# STM32_microcontroller_IOs.net
KiCad netlist of a schematic drawn in Altium Designer
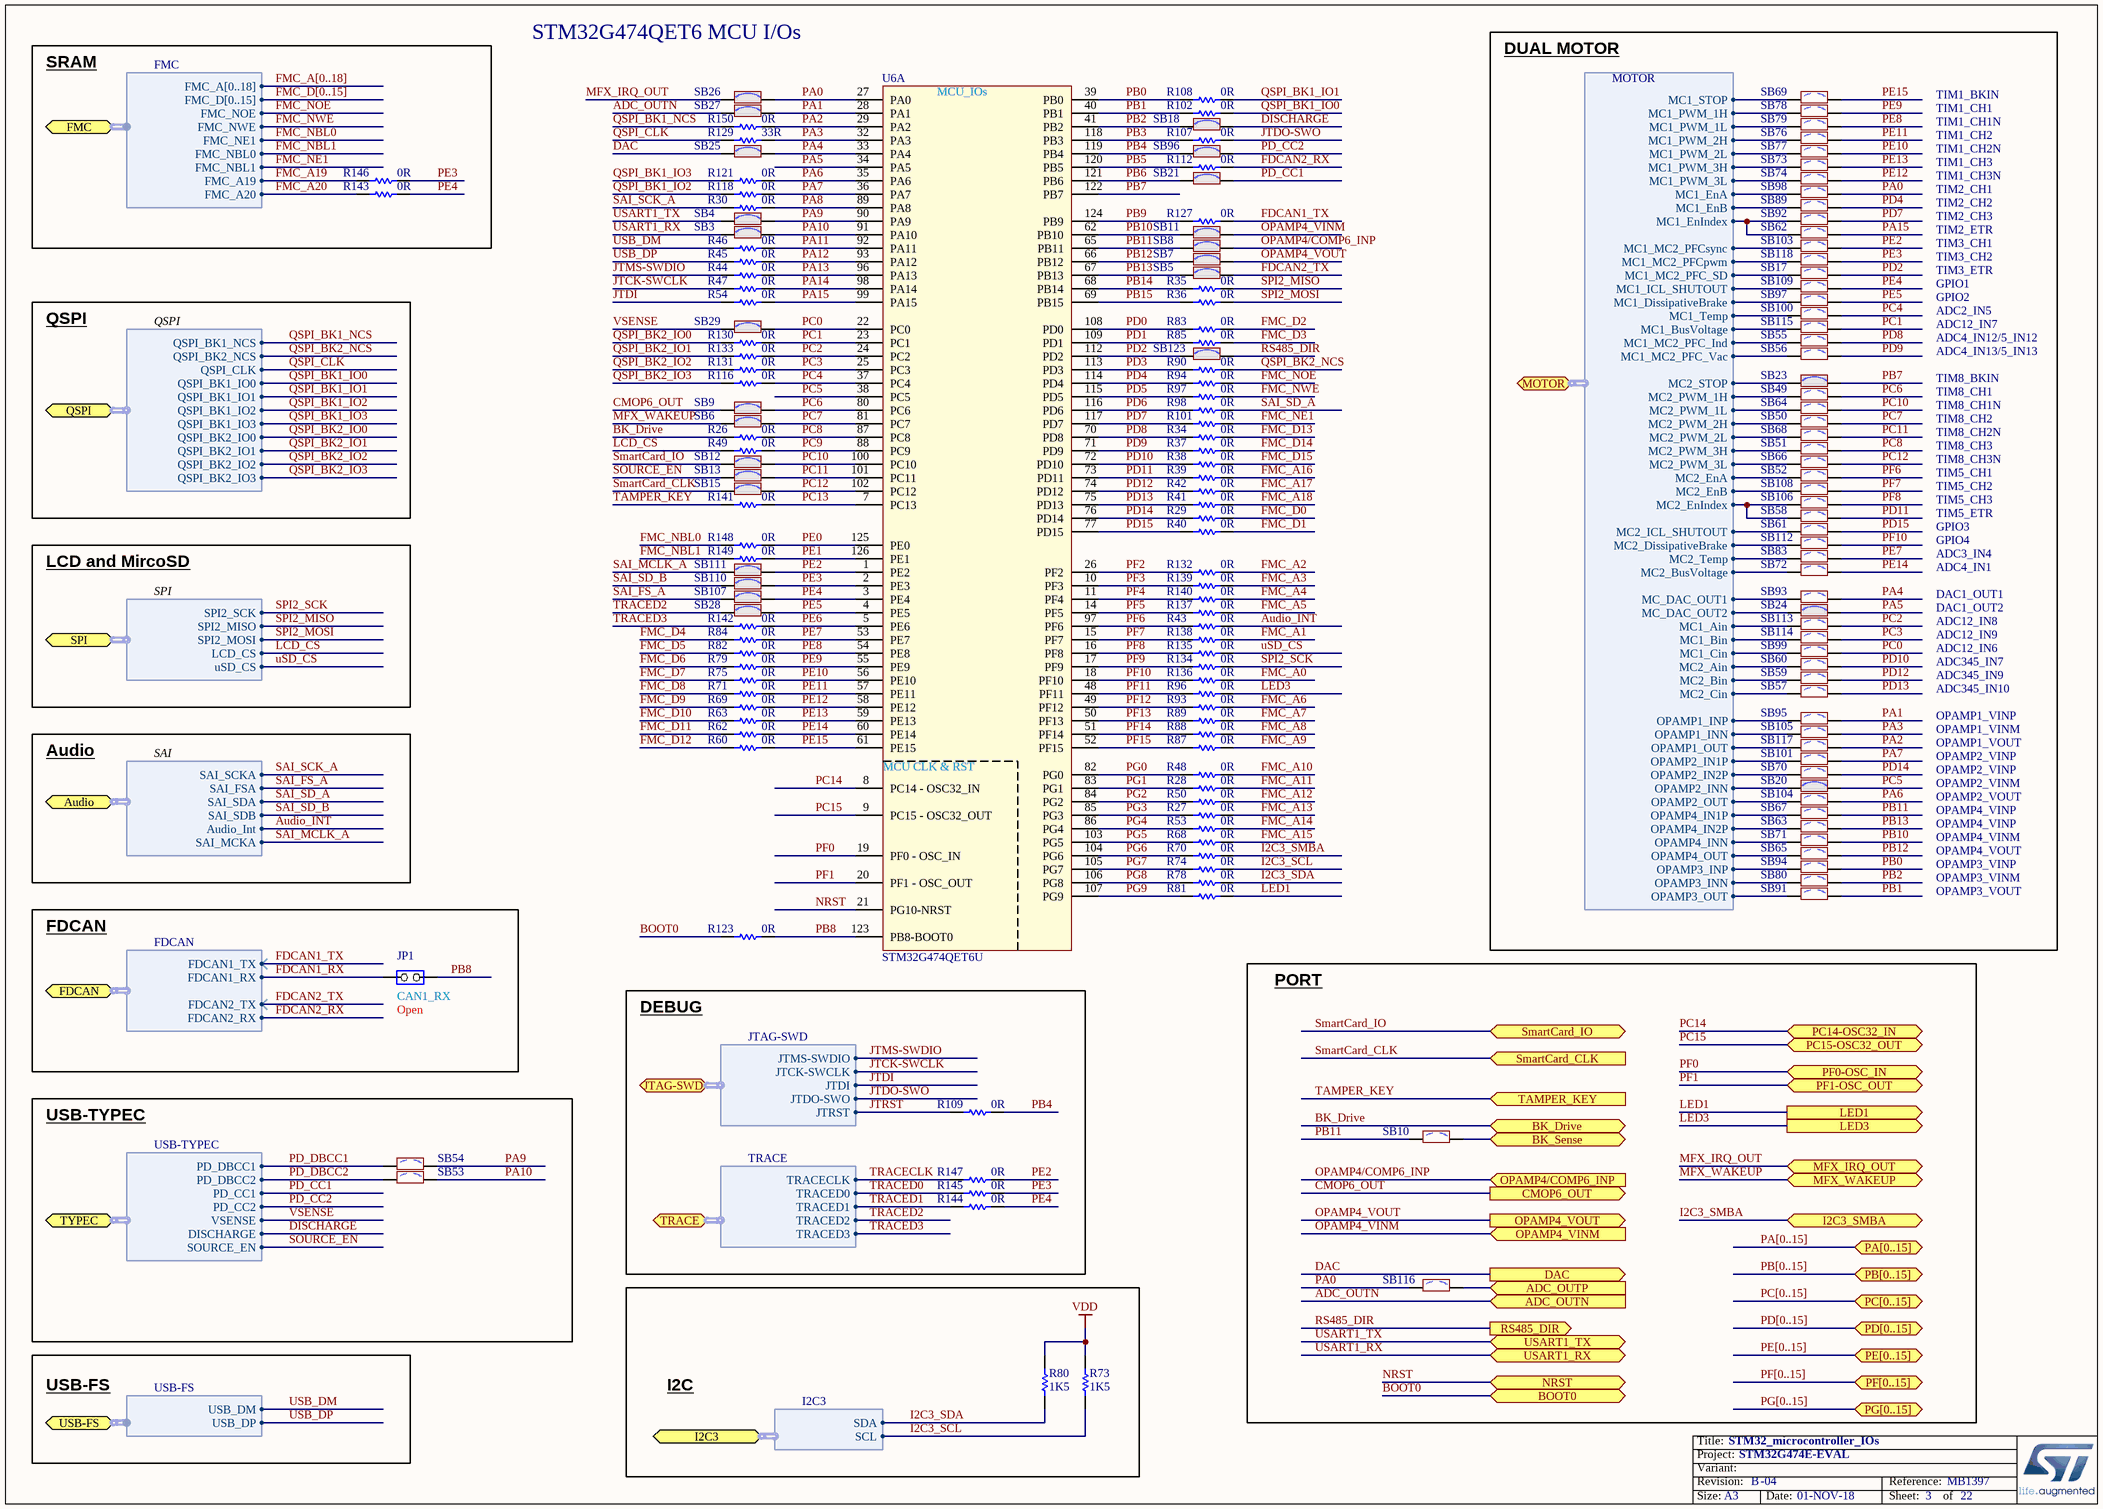
[diagram p0: STM32_microcontroller_IOs.SchDoc]

(export (version "E")
  (design (tool "Eeschema 10.0.6"))
  (components
    (comp (ref "JP1")
      (value "Jumper_Header 2x1")
      (footprint "CON_SAMTEC_TSW-102-07-G-S")
      (description "Header, 2x1, 2,54mm, VR, TH, Height 5.84mm/2.54mm")
      (fields
        (field (name "INTERNAL_PART_NUMBER") "MCD-00045")
        (field (name "MANUFACTURER_PART_NUMBER") "TSW-102-07-x-S")
        (field (name "PROVIDED_BY") "SUBCO")
      )
      (libsource (lib "MCD_PARTS_database") (part "Jumper_Header 2x1"))
    )
    (comp (ref "R26")
      (value "0R")
      (footprint "R0402")
      (description "Resistor,0R,0402,5%,1/16W")
      (fields
        (field (name "INTERNAL_PART_NUMBER") "MCD-00052")
        (field (name "MANUFACTURER_PART_NUMBER") "RC0402JR-070RL")
        (field (name "PROVIDED_BY") "SUBCO")
      )
      (libsource (lib "MCD_PARTS_database") (part "Resistor"))
    )
    (comp (ref "R27")
      (value "0R")
      (footprint "R0402")
      (description "Resistor,0R,0402,5%,1/16W")
      (fields (field (name "INTERNAL_PART_NUMBER") "MCD-00052") (field (name "Comment") "Resistor"))
      (libsource (lib "MCD_PARTS_database") (part "Resistor"))
    )
    (comp (ref "R28")
      (value "0R")
      (footprint "R0402")
      (description "Resistor,0R,0402,5%,1/16W")
      (fields (field (name "INTERNAL_PART_NUMBER") "MCD-00052") (field (name "Comment") "Resistor"))
      (libsource (lib "MCD_PARTS_database") (part "Resistor"))
    )
    (comp (ref "R29")
      (value "0R")
      (footprint "R0402")
      (description "Resistor,0R,0402,5%,1/16W")
      (fields (field (name "INTERNAL_PART_NUMBER") "MCD-00052") (field (name "Comment") "Resistor"))
      (libsource (lib "MCD_PARTS_database") (part "Resistor"))
    )
    (comp (ref "R30")
      (value "0R")
      (footprint "R0402")
      (description "Resistor,0R,0402,5%,1/16W")
      (fields
        (field (name "INTERNAL_PART_NUMBER") "MCD-00052")
        (field (name "MANUFACTURER_PART_NUMBER") "RC0402JR-070RL")
        (field (name "PROVIDED_BY") "SUBCO")
      )
      (libsource (lib "MCD_PARTS_database") (part "Resistor"))
    )
    (comp (ref "R34")
      (value "0R")
      (footprint "R0402")
      (description "Resistor,0R,0402,5%,1/16W")
      (fields (field (name "INTERNAL_PART_NUMBER") "MCD-00052") (field (name "Comment") "Resistor"))
      (libsource (lib "MCD_PARTS_database") (part "Resistor"))
    )
    (comp (ref "R35")
      (value "0R")
      (footprint "R0402")
      (description "Resistor,0R,0402,5%,1/16W")
      (fields
        (field (name "INTERNAL_PART_NUMBER") "MCD-00052")
        (field (name "MANUFACTURER_PART_NUMBER") "RC0402JR-070RL")
        (field (name "PROVIDED_BY") "SUBCO")
      )
      (libsource (lib "MCD_PARTS_database") (part "Resistor"))
    )
    (comp (ref "R36")
      (value "0R")
      (footprint "R0402")
      (description "Resistor,0R,0402,5%,1/16W")
      (fields
        (field (name "INTERNAL_PART_NUMBER") "MCD-00052")
        (field (name "MANUFACTURER_PART_NUMBER") "RC0402JR-070RL")
        (field (name "PROVIDED_BY") "SUBCO")
      )
      (libsource (lib "MCD_PARTS_database") (part "Resistor"))
    )
    (comp (ref "R37")
      (value "0R")
      (footprint "R0402")
      (description "Resistor,0R,0402,5%,1/16W")
      (fields (field (name "INTERNAL_PART_NUMBER") "MCD-00052") (field (name "Comment") "Resistor"))
      (libsource (lib "MCD_PARTS_database") (part "Resistor"))
    )
    (comp (ref "R38")
      (value "0R")
      (footprint "R0402")
      (description "Resistor,0R,0402,5%,1/16W")
      (fields (field (name "INTERNAL_PART_NUMBER") "MCD-00052") (field (name "Comment") "Resistor"))
      (libsource (lib "MCD_PARTS_database") (part "Resistor"))
    )
    (comp (ref "R39")
      (value "0R")
      (footprint "R0402")
      (description "Resistor,0R,0402,5%,1/16W")
      (fields (field (name "INTERNAL_PART_NUMBER") "MCD-00052") (field (name "Comment") "Resistor"))
      (libsource (lib "MCD_PARTS_database") (part "Resistor"))
    )
    (comp (ref "R40")
      (value "0R")
      (footprint "R0402")
      (description "Resistor,0R,0402,5%,1/16W")
      (fields (field (name "INTERNAL_PART_NUMBER") "MCD-00052") (field (name "Comment") "Resistor"))
      (libsource (lib "MCD_PARTS_database") (part "Resistor"))
    )
    (comp (ref "R41")
      (value "0R")
      (footprint "R0402")
      (description "Resistor,0R,0402,5%,1/16W")
      (fields (field (name "INTERNAL_PART_NUMBER") "MCD-00052") (field (name "Comment") "Resistor"))
      (libsource (lib "MCD_PARTS_database") (part "Resistor"))
    )
    (comp (ref "R42")
      (value "0R")
      (footprint "R0402")
      (description "Resistor,0R,0402,5%,1/16W")
      (fields (field (name "INTERNAL_PART_NUMBER") "MCD-00052") (field (name "Comment") "Resistor"))
      (libsource (lib "MCD_PARTS_database") (part "Resistor"))
    )
    (comp (ref "R43")
      (value "0R")
      (footprint "R0402")
      (description "Resistor,0R,0402,5%,1/16W")
      (fields
        (field (name "INTERNAL_PART_NUMBER") "MCD-00052")
        (field (name "MANUFACTURER_PART_NUMBER") "RC0402JR-070RL")
        (field (name "PROVIDED_BY") "SUBCO")
      )
      (libsource (lib "MCD_PARTS_database") (part "Resistor"))
    )
    (comp (ref "R44")
      (value "0R")
      (footprint "R0402")
      (description "Resistor,0R,0402,5%,1/16W")
      (fields
        (field (name "INTERNAL_PART_NUMBER") "MCD-00052")
        (field (name "MANUFACTURER_PART_NUMBER") "RC0402JR-070RL")
        (field (name "PROVIDED_BY") "SUBCO")
      )
      (libsource (lib "MCD_PARTS_database") (part "Resistor"))
    )
    (comp (ref "R45")
      (value "0R")
      (footprint "R0402")
      (description "Resistor,0R,0402,5%,1/16W")
      (fields
        (field (name "INTERNAL_PART_NUMBER") "MCD-00052")
        (field (name "MANUFACTURER_PART_NUMBER") "RC0402JR-070RL")
        (field (name "PROVIDED_BY") "SUBCO")
      )
      (libsource (lib "MCD_PARTS_database") (part "Resistor"))
    )
    (comp (ref "R46")
      (value "0R")
      (footprint "R0402")
      (description "Resistor,0R,0402,5%,1/16W")
      (fields
        (field (name "INTERNAL_PART_NUMBER") "MCD-00052")
        (field (name "MANUFACTURER_PART_NUMBER") "RC0402JR-070RL")
        (field (name "PROVIDED_BY") "SUBCO")
      )
      (libsource (lib "MCD_PARTS_database") (part "Resistor"))
    )
    (comp (ref "R47")
      (value "0R")
      (footprint "R0402")
      (description "Resistor,0R,0402,5%,1/16W")
      (fields
        (field (name "INTERNAL_PART_NUMBER") "MCD-00052")
        (field (name "MANUFACTURER_PART_NUMBER") "RC0402JR-070RL")
        (field (name "PROVIDED_BY") "SUBCO")
      )
      (libsource (lib "MCD_PARTS_database") (part "Resistor"))
    )
    (comp (ref "R48")
      (value "0R")
      (footprint "R0402")
      (description "Resistor,0R,0402,5%,1/16W")
      (fields (field (name "INTERNAL_PART_NUMBER") "MCD-00052") (field (name "Comment") "Resistor"))
      (libsource (lib "MCD_PARTS_database") (part "Resistor"))
    )
    (comp (ref "R49")
      (value "0R")
      (footprint "R0402")
      (description "Resistor,0R,0402,5%,1/16W")
      (fields
        (field (name "INTERNAL_PART_NUMBER") "MCD-00052")
        (field (name "MANUFACTURER_PART_NUMBER") "RC0402JR-070RL")
        (field (name "PROVIDED_BY") "SUBCO")
      )
      (libsource (lib "MCD_PARTS_database") (part "Resistor"))
    )
    (comp (ref "R50")
      (value "0R")
      (footprint "R0402")
      (description "Resistor,0R,0402,5%,1/16W")
      (fields (field (name "INTERNAL_PART_NUMBER") "MCD-00052") (field (name "Comment") "Resistor"))
      (libsource (lib "MCD_PARTS_database") (part "Resistor"))
    )
    (comp (ref "R53")
      (value "0R")
      (footprint "R0402")
      (description "Resistor,0R,0402,5%,1/16W")
      (fields (field (name "INTERNAL_PART_NUMBER") "MCD-00052") (field (name "Comment") "Resistor"))
      (libsource (lib "MCD_PARTS_database") (part "Resistor"))
    )
    (comp (ref "R54")
      (value "0R")
      (footprint "R0402")
      (description "Resistor,0R,0402,5%,1/16W")
      (fields
        (field (name "INTERNAL_PART_NUMBER") "MCD-00052")
        (field (name "MANUFACTURER_PART_NUMBER") "RC0402JR-070RL")
        (field (name "PROVIDED_BY") "SUBCO")
      )
      (libsource (lib "MCD_PARTS_database") (part "Resistor"))
    )
    (comp (ref "R60")
      (value "0R")
      (footprint "R0402")
      (description "Resistor,0R,0402,5%,1/16W")
      (fields (field (name "INTERNAL_PART_NUMBER") "MCD-00052") (field (name "Comment") "Resistor"))
      (libsource (lib "MCD_PARTS_database") (part "Resistor"))
    )
    (comp (ref "R62")
      (value "0R")
      (footprint "R0402")
      (description "Resistor,0R,0402,5%,1/16W")
      (fields (field (name "INTERNAL_PART_NUMBER") "MCD-00052") (field (name "Comment") "Resistor"))
      (libsource (lib "MCD_PARTS_database") (part "Resistor"))
    )
    (comp (ref "R63")
      (value "0R")
      (footprint "R0402")
      (description "Resistor,0R,0402,5%,1/16W")
      (fields (field (name "INTERNAL_PART_NUMBER") "MCD-00052") (field (name "Comment") "Resistor"))
      (libsource (lib "MCD_PARTS_database") (part "Resistor"))
    )
    (comp (ref "R68")
      (value "0R")
      (footprint "R0402")
      (description "Resistor,0R,0402,5%,1/16W")
      (fields (field (name "INTERNAL_PART_NUMBER") "MCD-00052") (field (name "Comment") "Resistor"))
      (libsource (lib "MCD_PARTS_database") (part "Resistor"))
    )
    (comp (ref "R69")
      (value "0R")
      (footprint "R0402")
      (description "Resistor,0R,0402,5%,1/16W")
      (fields (field (name "INTERNAL_PART_NUMBER") "MCD-00052") (field (name "Comment") "Resistor"))
      (libsource (lib "MCD_PARTS_database") (part "Resistor"))
    )
    (comp (ref "R70")
      (value "0R")
      (footprint "R0402")
      (description "Resistor,0R,0402,5%,1/16W")
      (fields
        (field (name "INTERNAL_PART_NUMBER") "MCD-00052")
        (field (name "MANUFACTURER_PART_NUMBER") "RC0402JR-070RL")
        (field (name "PROVIDED_BY") "SUBCO")
      )
      (libsource (lib "MCD_PARTS_database") (part "Resistor"))
    )
    (comp (ref "R71")
      (value "0R")
      (footprint "R0402")
      (description "Resistor,0R,0402,5%,1/16W")
      (fields (field (name "INTERNAL_PART_NUMBER") "MCD-00052") (field (name "Comment") "Resistor"))
      (libsource (lib "MCD_PARTS_database") (part "Resistor"))
    )
    (comp (ref "R73")
      (value "1K5")
      (footprint "R0603")
      (description "Resistor,1K5,0603,1%,1/10W")
      (fields
        (field (name "INTERNAL_PART_NUMBER") "MCD-00217")
        (field (name "MANUFACTURER_PART_NUMBER") "RC0603FR-071K5L")
        (field (name "PROVIDED_BY") "SUBCO")
      )
      (libsource (lib "MCD_PARTS_database") (part "Resistor"))
    )
    (comp (ref "R74")
      (value "0R")
      (footprint "R0402")
      (description "Resistor,0R,0402,5%,1/16W")
      (fields
        (field (name "INTERNAL_PART_NUMBER") "MCD-00052")
        (field (name "MANUFACTURER_PART_NUMBER") "RC0402JR-070RL")
        (field (name "PROVIDED_BY") "SUBCO")
      )
      (libsource (lib "MCD_PARTS_database") (part "Resistor"))
    )
    (comp (ref "R75")
      (value "0R")
      (footprint "R0402")
      (description "Resistor,0R,0402,5%,1/16W")
      (fields (field (name "INTERNAL_PART_NUMBER") "MCD-00052") (field (name "Comment") "Resistor"))
      (libsource (lib "MCD_PARTS_database") (part "Resistor"))
    )
    (comp (ref "R78")
      (value "0R")
      (footprint "R0402")
      (description "Resistor,0R,0402,5%,1/16W")
      (fields
        (field (name "INTERNAL_PART_NUMBER") "MCD-00052")
        (field (name "MANUFACTURER_PART_NUMBER") "RC0402JR-070RL")
        (field (name "PROVIDED_BY") "SUBCO")
      )
      (libsource (lib "MCD_PARTS_database") (part "Resistor"))
    )
    (comp (ref "R79")
      (value "0R")
      (footprint "R0402")
      (description "Resistor,0R,0402,5%,1/16W")
      (fields (field (name "INTERNAL_PART_NUMBER") "MCD-00052") (field (name "Comment") "Resistor"))
      (libsource (lib "MCD_PARTS_database") (part "Resistor"))
    )
    (comp (ref "R80")
      (value "1K5")
      (footprint "R0603")
      (description "Resistor,1K5,0603,1%,1/10W")
      (fields
        (field (name "INTERNAL_PART_NUMBER") "MCD-00217")
        (field (name "MANUFACTURER_PART_NUMBER") "RC0603FR-071K5L")
        (field (name "PROVIDED_BY") "SUBCO")
      )
      (libsource (lib "MCD_PARTS_database") (part "Resistor"))
    )
    (comp (ref "R81")
      (value "0R")
      (footprint "R0402")
      (description "Resistor,0R,0402,5%,1/16W")
      (fields
        (field (name "INTERNAL_PART_NUMBER") "MCD-00052")
        (field (name "MANUFACTURER_PART_NUMBER") "RC0402JR-070RL")
        (field (name "PROVIDED_BY") "SUBCO")
      )
      (libsource (lib "MCD_PARTS_database") (part "Resistor"))
    )
    (comp (ref "R82")
      (value "0R")
      (footprint "R0402")
      (description "Resistor,0R,0402,5%,1/16W")
      (fields (field (name "INTERNAL_PART_NUMBER") "MCD-00052") (field (name "Comment") "Resistor"))
      (libsource (lib "MCD_PARTS_database") (part "Resistor"))
    )
    (comp (ref "R83")
      (value "0R")
      (footprint "R0402")
      (description "Resistor,0R,0402,5%,1/16W")
      (fields (field (name "INTERNAL_PART_NUMBER") "MCD-00052") (field (name "Comment") "Resistor"))
      (libsource (lib "MCD_PARTS_database") (part "Resistor"))
    )
    (comp (ref "R84")
      (value "0R")
      (footprint "R0402")
      (description "Resistor,0R,0402,5%,1/16W")
      (fields (field (name "INTERNAL_PART_NUMBER") "MCD-00052") (field (name "Comment") "Resistor"))
      (libsource (lib "MCD_PARTS_database") (part "Resistor"))
    )
    (comp (ref "R85")
      (value "0R")
      (footprint "R0402")
      (description "Resistor,0R,0402,5%,1/16W")
      (fields (field (name "INTERNAL_PART_NUMBER") "MCD-00052") (field (name "Comment") "Resistor"))
      (libsource (lib "MCD_PARTS_database") (part "Resistor"))
    )
    (comp (ref "R87")
      (value "0R")
      (footprint "R0402")
      (description "Resistor,0R,0402,5%,1/16W")
      (fields (field (name "INTERNAL_PART_NUMBER") "MCD-00052") (field (name "Comment") "Resistor"))
      (libsource (lib "MCD_PARTS_database") (part "Resistor"))
    )
    (comp (ref "R88")
      (value "0R")
      (footprint "R0402")
      (description "Resistor,0R,0402,5%,1/16W")
      (fields (field (name "INTERNAL_PART_NUMBER") "MCD-00052") (field (name "Comment") "Resistor"))
      (libsource (lib "MCD_PARTS_database") (part "Resistor"))
    )
    (comp (ref "R89")
      (value "0R")
      (footprint "R0402")
      (description "Resistor,0R,0402,5%,1/16W")
      (fields (field (name "INTERNAL_PART_NUMBER") "MCD-00052") (field (name "Comment") "Resistor"))
      (libsource (lib "MCD_PARTS_database") (part "Resistor"))
    )
    (comp (ref "R90")
      (value "0R")
      (footprint "R0402")
      (description "Resistor,0R,0402,5%,1/16W")
      (fields (field (name "INTERNAL_PART_NUMBER") "MCD-00052") (field (name "Comment") "Resistor"))
      (libsource (lib "MCD_PARTS_database") (part "Resistor"))
    )
    (comp (ref "R93")
      (value "0R")
      (footprint "R0402")
      (description "Resistor,0R,0402,5%,1/16W")
      (fields (field (name "INTERNAL_PART_NUMBER") "MCD-00052") (field (name "Comment") "Resistor"))
      (libsource (lib "MCD_PARTS_database") (part "Resistor"))
    )
    (comp (ref "R94")
      (value "0R")
      (footprint "R0402")
      (description "Resistor,0R,0402,5%,1/16W")
      (fields
        (field (name "INTERNAL_PART_NUMBER") "MCD-00052")
        (field (name "MANUFACTURER_PART_NUMBER") "RC0402JR-070RL")
        (field (name "PROVIDED_BY") "SUBCO")
      )
      (libsource (lib "MCD_PARTS_database") (part "Resistor"))
    )
    (comp (ref "R96")
      (value "0R")
      (footprint "R0402")
      (description "Resistor,0R,0402,5%,1/16W")
      (fields
        (field (name "INTERNAL_PART_NUMBER") "MCD-00052")
        (field (name "MANUFACTURER_PART_NUMBER") "RC0402JR-070RL")
        (field (name "PROVIDED_BY") "SUBCO")
      )
      (libsource (lib "MCD_PARTS_database") (part "Resistor"))
    )
    (comp (ref "R97")
      (value "0R")
      (footprint "R0402")
      (description "Resistor,0R,0402,5%,1/16W")
      (fields
        (field (name "INTERNAL_PART_NUMBER") "MCD-00052")
        (field (name "MANUFACTURER_PART_NUMBER") "RC0402JR-070RL")
        (field (name "PROVIDED_BY") "SUBCO")
      )
      (libsource (lib "MCD_PARTS_database") (part "Resistor"))
    )
    (comp (ref "R98")
      (value "0R")
      (footprint "R0402")
      (description "Resistor,0R,0402,5%,1/16W")
      (fields
        (field (name "INTERNAL_PART_NUMBER") "MCD-00052")
        (field (name "MANUFACTURER_PART_NUMBER") "RC0402JR-070RL")
        (field (name "PROVIDED_BY") "SUBCO")
      )
      (libsource (lib "MCD_PARTS_database") (part "Resistor"))
    )
    (comp (ref "R101")
      (value "0R")
      (footprint "R0402")
      (description "Resistor,0R,0402,5%,1/16W")
      (fields
        (field (name "INTERNAL_PART_NUMBER") "MCD-00052")
        (field (name "MANUFACTURER_PART_NUMBER") "RC0402JR-070RL")
        (field (name "PROVIDED_BY") "SUBCO")
      )
      (libsource (lib "MCD_PARTS_database") (part "Resistor"))
    )
    (comp (ref "R102")
      (value "0R")
      (footprint "R0402")
      (description "Resistor,0R,0402,5%,1/16W")
      (fields (field (name "INTERNAL_PART_NUMBER") "MCD-00052") (field (name "Comment") "Resistor"))
      (libsource (lib "MCD_PARTS_database") (part "Resistor"))
    )
    (comp (ref "R107")
      (value "0R")
      (footprint "R0402")
      (description "Resistor,0R,0402,5%,1/16W")
      (fields
        (field (name "INTERNAL_PART_NUMBER") "MCD-00052")
        (field (name "MANUFACTURER_PART_NUMBER") "RC0402JR-070RL")
        (field (name "PROVIDED_BY") "SUBCO")
      )
      (libsource (lib "MCD_PARTS_database") (part "Resistor"))
    )
    (comp (ref "R108")
      (value "0R")
      (footprint "R0402")
      (description "Resistor,0R,0402,5%,1/16W")
      (fields (field (name "INTERNAL_PART_NUMBER") "MCD-00052") (field (name "Comment") "Resistor"))
      (libsource (lib "MCD_PARTS_database") (part "Resistor"))
    )
    (comp (ref "R109")
      (value "0R")
      (footprint "R0402")
      (description "Resistor,0R,0402,5%,1/16W")
      (fields
        (field (name "INTERNAL_PART_NUMBER") "MCD-00052")
        (field (name "MANUFACTURER_PART_NUMBER") "RC0402JR-070RL")
        (field (name "PROVIDED_BY") "SUBCO")
      )
      (libsource (lib "MCD_PARTS_database") (part "Resistor"))
    )
    (comp (ref "R112")
      (value "0R")
      (footprint "R0402")
      (description "Resistor,0R,0402,5%,1/16W")
      (fields
        (field (name "INTERNAL_PART_NUMBER") "MCD-00052")
        (field (name "MANUFACTURER_PART_NUMBER") "RC0402JR-070RL")
        (field (name "PROVIDED_BY") "SUBCO")
      )
      (libsource (lib "MCD_PARTS_database") (part "Resistor"))
    )
    (comp (ref "R116")
      (value "0R")
      (footprint "R0402")
      (description "Resistor,0R,0402,5%,1/16W")
      (fields (field (name "INTERNAL_PART_NUMBER") "MCD-00052") (field (name "Comment") "Resistor"))
      (libsource (lib "MCD_PARTS_database") (part "Resistor"))
    )
    (comp (ref "R118")
      (value "0R")
      (footprint "R0402")
      (description "Resistor,0R,0402,5%,1/16W")
      (fields (field (name "INTERNAL_PART_NUMBER") "MCD-00052") (field (name "Comment") "Resistor"))
      (libsource (lib "MCD_PARTS_database") (part "Resistor"))
    )
    (comp (ref "R121")
      (value "0R")
      (footprint "R0402")
      (description "Resistor,0R,0402,5%,1/16W")
      (fields (field (name "INTERNAL_PART_NUMBER") "MCD-00052") (field (name "Comment") "Resistor"))
      (libsource (lib "MCD_PARTS_database") (part "Resistor"))
    )
    (comp (ref "R123")
      (value "0R")
      (footprint "R0402")
      (description "Resistor,0R,0402,5%,1/16W")
      (fields
        (field (name "INTERNAL_PART_NUMBER") "MCD-00052")
        (field (name "MANUFACTURER_PART_NUMBER") "RC0402JR-070RL")
        (field (name "PROVIDED_BY") "SUBCO")
      )
      (libsource (lib "MCD_PARTS_database") (part "Resistor"))
    )
    (comp (ref "R127")
      (value "0R")
      (footprint "R0402")
      (description "Resistor,0R,0402,5%,1/16W")
      (fields
        (field (name "INTERNAL_PART_NUMBER") "MCD-00052")
        (field (name "MANUFACTURER_PART_NUMBER") "RC0402JR-070RL")
        (field (name "PROVIDED_BY") "SUBCO")
      )
      (libsource (lib "MCD_PARTS_database") (part "Resistor"))
    )
    (comp (ref "R129")
      (value "33R")
      (footprint "R0402")
      (description "Resistor,33R,0402,1%,1/16W")
      (fields
        (field (name "INTERNAL_PART_NUMBER") "MCD-00455")
        (field (name "MANUFACTURER_PART_NUMBER") "RC0402FR-0733RL")
        (field (name "PROVIDED_BY") "SUBCO")
      )
      (libsource (lib "MCD_PARTS_database") (part "Resistor"))
    )
    (comp (ref "R130")
      (value "0R")
      (footprint "R0402")
      (description "Resistor,0R,0402,5%,1/16W")
      (fields (field (name "INTERNAL_PART_NUMBER") "MCD-00052") (field (name "Comment") "Resistor"))
      (libsource (lib "MCD_PARTS_database") (part "Resistor"))
    )
    (comp (ref "R131")
      (value "0R")
      (footprint "R0402")
      (description "Resistor,0R,0402,5%,1/16W")
      (fields (field (name "INTERNAL_PART_NUMBER") "MCD-00052") (field (name "Comment") "Resistor"))
      (libsource (lib "MCD_PARTS_database") (part "Resistor"))
    )
    (comp (ref "R132")
      (value "0R")
      (footprint "R0402")
      (description "Resistor,0R,0402,5%,1/16W")
      (fields (field (name "INTERNAL_PART_NUMBER") "MCD-00052") (field (name "Comment") "Resistor"))
      (libsource (lib "MCD_PARTS_database") (part "Resistor"))
    )
    (comp (ref "R133")
      (value "0R")
      (footprint "R0402")
      (description "Resistor,0R,0402,5%,1/16W")
      (fields (field (name "INTERNAL_PART_NUMBER") "MCD-00052") (field (name "Comment") "Resistor"))
      (libsource (lib "MCD_PARTS_database") (part "Resistor"))
    )
    (comp (ref "R134")
      (value "0R")
      (footprint "R0402")
      (description "Resistor,0R,0402,5%,1/16W")
      (fields
        (field (name "INTERNAL_PART_NUMBER") "MCD-00052")
        (field (name "MANUFACTURER_PART_NUMBER") "RC0402JR-070RL")
        (field (name "PROVIDED_BY") "SUBCO")
      )
      (libsource (lib "MCD_PARTS_database") (part "Resistor"))
    )
    (comp (ref "R135")
      (value "0R")
      (footprint "R0402")
      (description "Resistor,0R,0402,5%,1/16W")
      (fields
        (field (name "INTERNAL_PART_NUMBER") "MCD-00052")
        (field (name "MANUFACTURER_PART_NUMBER") "RC0402JR-070RL")
        (field (name "PROVIDED_BY") "SUBCO")
      )
      (libsource (lib "MCD_PARTS_database") (part "Resistor"))
    )
    (comp (ref "R136")
      (value "0R")
      (footprint "R0402")
      (description "Resistor,0R,0402,5%,1/16W")
      (fields (field (name "INTERNAL_PART_NUMBER") "MCD-00052") (field (name "Comment") "Resistor"))
      (libsource (lib "MCD_PARTS_database") (part "Resistor"))
    )
    (comp (ref "R137")
      (value "0R")
      (footprint "R0402")
      (description "Resistor,0R,0402,5%,1/16W")
      (fields (field (name "INTERNAL_PART_NUMBER") "MCD-00052") (field (name "Comment") "Resistor"))
      (libsource (lib "MCD_PARTS_database") (part "Resistor"))
    )
    (comp (ref "R138")
      (value "0R")
      (footprint "R0402")
      (description "Resistor,0R,0402,5%,1/16W")
      (fields (field (name "INTERNAL_PART_NUMBER") "MCD-00052") (field (name "Comment") "Resistor"))
      (libsource (lib "MCD_PARTS_database") (part "Resistor"))
    )
    (comp (ref "R139")
      (value "0R")
      (footprint "R0402")
      (description "Resistor,0R,0402,5%,1/16W")
      (fields (field (name "INTERNAL_PART_NUMBER") "MCD-00052") (field (name "Comment") "Resistor"))
      (libsource (lib "MCD_PARTS_database") (part "Resistor"))
    )
    (comp (ref "R140")
      (value "0R")
      (footprint "R0402")
      (description "Resistor,0R,0402,5%,1/16W")
      (fields (field (name "INTERNAL_PART_NUMBER") "MCD-00052") (field (name "Comment") "Resistor"))
      (libsource (lib "MCD_PARTS_database") (part "Resistor"))
    )
    (comp (ref "R141")
      (value "0R")
      (footprint "R0402")
      (description "Resistor,0R,0402,5%,1/16W")
      (fields
        (field (name "INTERNAL_PART_NUMBER") "MCD-00052")
        (field (name "MANUFACTURER_PART_NUMBER") "RC0402JR-070RL")
        (field (name "PROVIDED_BY") "SUBCO")
      )
      (libsource (lib "MCD_PARTS_database") (part "Resistor"))
    )
    (comp (ref "R142")
      (value "0R")
      (footprint "R0402")
      (description "Resistor,0R,0402,5%,1/16W")
      (fields
        (field (name "INTERNAL_PART_NUMBER") "MCD-00052")
        (field (name "MANUFACTURER_PART_NUMBER") "RC0402JR-070RL")
        (field (name "PROVIDED_BY") "SUBCO")
      )
      (libsource (lib "MCD_PARTS_database") (part "Resistor"))
    )
    (comp (ref "R143")
      (value "0R")
      (footprint "R0402")
      (description "Resistor,0R,0402,5%,1/16W")
      (fields (field (name "INTERNAL_PART_NUMBER") "MCD-00052") (field (name "Comment") "Resistor"))
      (libsource (lib "MCD_PARTS_database") (part "Resistor"))
    )
    (comp (ref "R144")
      (value "0R")
      (footprint "R0402")
      (description "Resistor,0R,0402,5%,1/16W")
      (fields
        (field (name "INTERNAL_PART_NUMBER") "MCD-00052")
        (field (name "MANUFACTURER_PART_NUMBER") "RC0402JR-070RL")
        (field (name "PROVIDED_BY") "SUBCO")
      )
      (libsource (lib "MCD_PARTS_database") (part "Resistor"))
    )
    (comp (ref "R145")
      (value "0R")
      (footprint "R0402")
      (description "Resistor,0R,0402,5%,1/16W")
      (fields
        (field (name "INTERNAL_PART_NUMBER") "MCD-00052")
        (field (name "MANUFACTURER_PART_NUMBER") "RC0402JR-070RL")
        (field (name "PROVIDED_BY") "SUBCO")
      )
      (libsource (lib "MCD_PARTS_database") (part "Resistor"))
    )
    (comp (ref "R146")
      (value "0R")
      (footprint "R0402")
      (description "Resistor,0R,0402,5%,1/16W")
      (fields (field (name "INTERNAL_PART_NUMBER") "MCD-00052") (field (name "Comment") "Resistor"))
      (libsource (lib "MCD_PARTS_database") (part "Resistor"))
    )
    (comp (ref "R147")
      (value "0R")
      (footprint "R0402")
      (description "Resistor,0R,0402,5%,1/16W")
      (fields
        (field (name "INTERNAL_PART_NUMBER") "MCD-00052")
        (field (name "MANUFACTURER_PART_NUMBER") "RC0402JR-070RL")
        (field (name "PROVIDED_BY") "SUBCO")
      )
      (libsource (lib "MCD_PARTS_database") (part "Resistor"))
    )
    (comp (ref "R148")
      (value "0R")
      (footprint "R0402")
      (description "Resistor,0R,0402,5%,1/16W")
      (fields
        (field (name "INTERNAL_PART_NUMBER") "MCD-00052")
        (field (name "MANUFACTURER_PART_NUMBER") "RC0402JR-070RL")
        (field (name "PROVIDED_BY") "SUBCO")
      )
      (libsource (lib "MCD_PARTS_database") (part "Resistor"))
    )
    (comp (ref "R149")
      (value "0R")
      (footprint "R0402")
      (description "Resistor,0R,0402,5%,1/16W")
      (fields
        (field (name "INTERNAL_PART_NUMBER") "MCD-00052")
        (field (name "MANUFACTURER_PART_NUMBER") "RC0402JR-070RL")
        (field (name "PROVIDED_BY") "SUBCO")
      )
      (libsource (lib "MCD_PARTS_database") (part "Resistor"))
    )
    (comp (ref "R150")
      (value "0R")
      (footprint "R0402")
      (description "Resistor,0R,0402,5%,1/16W")
      (fields (field (name "INTERNAL_PART_NUMBER") "MCD-00052") (field (name "Comment") "Resistor"))
      (libsource (lib "MCD_PARTS_database") (part "Resistor"))
    )
    (comp (ref "SB3")
      (value "SB_ON")
      (footprint "SOLDER-BRIDGE_R0603-0R")
      (description "Solder Bridge ON")
      (fields
        (field (name "INTERNAL_PART_NUMBER") "MCD-00071")
        (field (name "MANUFACTURER_PART_NUMBER") "RC0603JR-070RL")
        (field (name "PROVIDED_BY") "SUBCO")
      )
      (libsource (lib "MCD_PARTS_database") (part "SB_ON"))
    )
    (comp (ref "SB4")
      (value "SB_ON")
      (footprint "SOLDER-BRIDGE_R0603-0R")
      (description "Solder Bridge ON")
      (fields
        (field (name "INTERNAL_PART_NUMBER") "MCD-00071")
        (field (name "MANUFACTURER_PART_NUMBER") "RC0603JR-070RL")
        (field (name "PROVIDED_BY") "SUBCO")
      )
      (libsource (lib "MCD_PARTS_database") (part "SB_ON"))
    )
    (comp (ref "SB5")
      (value "SB_ON")
      (footprint "SOLDER-BRIDGE_R0603-0R")
      (description "Solder Bridge ON")
      (fields
        (field (name "INTERNAL_PART_NUMBER") "MCD-00071")
        (field (name "MANUFACTURER_PART_NUMBER") "RC0603JR-070RL")
        (field (name "PROVIDED_BY") "SUBCO")
      )
      (libsource (lib "MCD_PARTS_database") (part "SB_ON"))
    )
    (comp (ref "SB6")
      (value "SB_ON")
      (footprint "SOLDER-BRIDGE_R0603-0R")
      (description "Solder Bridge ON")
      (fields
        (field (name "INTERNAL_PART_NUMBER") "MCD-00071")
        (field (name "MANUFACTURER_PART_NUMBER") "RC0603JR-070RL")
        (field (name "PROVIDED_BY") "SUBCO")
      )
      (libsource (lib "MCD_PARTS_database") (part "SB_ON"))
    )
    (comp (ref "SB7")
      (value "SB_ON")
      (footprint "SOLDER-BRIDGE_R0603-0R")
      (description "Solder Bridge ON")
      (fields
        (field (name "INTERNAL_PART_NUMBER") "MCD-00071")
        (field (name "MANUFACTURER_PART_NUMBER") "RC0603JR-070RL")
        (field (name "PROVIDED_BY") "SUBCO")
      )
      (libsource (lib "MCD_PARTS_database") (part "SB_ON"))
    )
    (comp (ref "SB8")
      (value "SB_ON")
      (footprint "SOLDER-BRIDGE_R0603-0R")
      (description "Solder Bridge ON")
      (fields
        (field (name "INTERNAL_PART_NUMBER") "MCD-00071")
        (field (name "MANUFACTURER_PART_NUMBER") "RC0603JR-070RL")
        (field (name "PROVIDED_BY") "SUBCO")
      )
      (libsource (lib "MCD_PARTS_database") (part "SB_ON"))
    )
    (comp (ref "SB9")
      (value "SB_ON")
      (footprint "SOLDER-BRIDGE_R0603-0R")
      (description "Solder Bridge ON")
      (fields
        (field (name "INTERNAL_PART_NUMBER") "MCD-00071")
        (field (name "MANUFACTURER_PART_NUMBER") "RC0603JR-070RL")
        (field (name "PROVIDED_BY") "SUBCO")
      )
      (libsource (lib "MCD_PARTS_database") (part "SB_ON"))
    )
    (comp (ref "SB10")
      (value "SB_OFF")
      (footprint "SOLDER-BRIDGE_R0603-0R")
      (description "Solder Bridge OFF")
      (fields
        (field (name "INTERNAL_PART_NUMBER") "MCD-00072")
        (field (name "MANUFACTURER_PART_NUMBER") "RC0603JR-070RL")
        (field (name "PROVIDED_BY") "SUBCO")
      )
      (libsource (lib "MCD_PARTS_database") (part "SB_OFF"))
    )
    (comp (ref "SB11")
      (value "SB_ON")
      (footprint "SOLDER-BRIDGE_R0603-0R")
      (description "Solder Bridge ON")
      (fields
        (field (name "INTERNAL_PART_NUMBER") "MCD-00071")
        (field (name "MANUFACTURER_PART_NUMBER") "RC0603JR-070RL")
        (field (name "PROVIDED_BY") "SUBCO")
      )
      (libsource (lib "MCD_PARTS_database") (part "SB_ON"))
    )
    (comp (ref "SB12")
      (value "SB_ON")
      (footprint "SOLDER-BRIDGE_R0603-0R")
      (description "Solder Bridge ON")
      (fields
        (field (name "INTERNAL_PART_NUMBER") "MCD-00071")
        (field (name "MANUFACTURER_PART_NUMBER") "RC0603JR-070RL")
        (field (name "PROVIDED_BY") "SUBCO")
      )
      (libsource (lib "MCD_PARTS_database") (part "SB_ON"))
    )
    (comp (ref "SB13")
      (value "SB_ON")
      (footprint "SOLDER-BRIDGE_R0603-0R")
      (description "Solder Bridge ON")
      (fields
        (field (name "INTERNAL_PART_NUMBER") "MCD-00071")
        (field (name "MANUFACTURER_PART_NUMBER") "RC0603JR-070RL")
        (field (name "PROVIDED_BY") "SUBCO")
      )
      (libsource (lib "MCD_PARTS_database") (part "SB_ON"))
    )
    (comp (ref "SB15")
      (value "SB_ON")
      (footprint "SOLDER-BRIDGE_R0603-0R")
      (description "Solder Bridge ON")
      (fields
        (field (name "INTERNAL_PART_NUMBER") "MCD-00071")
        (field (name "MANUFACTURER_PART_NUMBER") "RC0603JR-070RL")
        (field (name "PROVIDED_BY") "SUBCO")
      )
      (libsource (lib "MCD_PARTS_database") (part "SB_ON"))
    )
    (comp (ref "SB17")
      (value "SB_OFF")
      (footprint "SOLDER-BRIDGE_R0603-0R")
      (description "Solder Bridge OFF")
      (fields
        (field (name "INTERNAL_PART_NUMBER") "MCD-00072")
        (field (name "MANUFACTURER_PART_NUMBER") "RC0603JR-070RL")
        (field (name "PROVIDED_BY") "SUBCO")
      )
      (libsource (lib "MCD_PARTS_database") (part "SB_OFF"))
    )
    (comp (ref "SB18")
      (value "SB_ON")
      (footprint "SOLDER-BRIDGE_R0603-0R")
      (description "Solder Bridge ON")
      (fields
        (field (name "INTERNAL_PART_NUMBER") "MCD-00071")
        (field (name "MANUFACTURER_PART_NUMBER") "RC0603JR-070RL")
        (field (name "PROVIDED_BY") "SUBCO")
      )
      (libsource (lib "MCD_PARTS_database") (part "SB_ON"))
    )
    (comp (ref "SB20")
      (value "SB_ON")
      (footprint "SOLDER-BRIDGE_R0603-0R")
      (description "Solder Bridge ON")
      (fields
        (field (name "INTERNAL_PART_NUMBER") "MCD-00071")
        (field (name "MANUFACTURER_PART_NUMBER") "RC0603JR-070RL")
        (field (name "PROVIDED_BY") "SUBCO")
      )
      (libsource (lib "MCD_PARTS_database") (part "SB_ON"))
    )
    (comp (ref "SB21")
      (value "SB_ON")
      (footprint "SOLDER-BRIDGE_R0603-0R")
      (description "Solder Bridge ON")
      (fields
        (field (name "INTERNAL_PART_NUMBER") "MCD-00071")
        (field (name "MANUFACTURER_PART_NUMBER") "RC0603JR-070RL")
        (field (name "PROVIDED_BY") "SUBCO")
      )
      (libsource (lib "MCD_PARTS_database") (part "SB_ON"))
    )
    (comp (ref "SB23")
      (value "SB_ON")
      (footprint "SOLDER-BRIDGE_R0603-0R")
      (description "Solder Bridge ON")
      (fields
        (field (name "INTERNAL_PART_NUMBER") "MCD-00071")
        (field (name "MANUFACTURER_PART_NUMBER") "RC0603JR-070RL")
        (field (name "PROVIDED_BY") "SUBCO")
      )
      (libsource (lib "MCD_PARTS_database") (part "SB_ON"))
    )
    (comp (ref "SB24")
      (value "SB_ON")
      (footprint "SOLDER-BRIDGE_R0603-0R")
      (description "Solder Bridge ON")
      (fields
        (field (name "INTERNAL_PART_NUMBER") "MCD-00071")
        (field (name "MANUFACTURER_PART_NUMBER") "RC0603JR-070RL")
        (field (name "PROVIDED_BY") "SUBCO")
      )
      (libsource (lib "MCD_PARTS_database") (part "SB_ON"))
    )
    (comp (ref "SB25")
      (value "SB_ON")
      (footprint "SOLDER-BRIDGE_R0603-0R")
      (description "Solder Bridge ON")
      (fields
        (field (name "INTERNAL_PART_NUMBER") "MCD-00071")
        (field (name "MANUFACTURER_PART_NUMBER") "RC0603JR-070RL")
        (field (name "PROVIDED_BY") "SUBCO")
      )
      (libsource (lib "MCD_PARTS_database") (part "SB_ON"))
    )
    (comp (ref "SB26")
      (value "SB_ON")
      (footprint "SOLDER-BRIDGE_R0603-0R")
      (description "Solder Bridge ON")
      (fields
        (field (name "INTERNAL_PART_NUMBER") "MCD-00071")
        (field (name "MANUFACTURER_PART_NUMBER") "RC0603JR-070RL")
        (field (name "PROVIDED_BY") "SUBCO")
      )
      (libsource (lib "MCD_PARTS_database") (part "SB_ON"))
    )
    (comp (ref "SB27")
      (value "SB_ON")
      (footprint "SOLDER-BRIDGE_R0603-0R")
      (description "Solder Bridge ON")
      (fields
        (field (name "INTERNAL_PART_NUMBER") "MCD-00071")
        (field (name "MANUFACTURER_PART_NUMBER") "RC0603JR-070RL")
        (field (name "PROVIDED_BY") "SUBCO")
      )
      (libsource (lib "MCD_PARTS_database") (part "SB_ON"))
    )
    (comp (ref "SB28")
      (value "SB_ON")
      (footprint "SOLDER-BRIDGE_R0603-0R")
      (description "Solder Bridge ON")
      (fields
        (field (name "INTERNAL_PART_NUMBER") "MCD-00071")
        (field (name "MANUFACTURER_PART_NUMBER") "RC0603JR-070RL")
        (field (name "PROVIDED_BY") "SUBCO")
      )
      (libsource (lib "MCD_PARTS_database") (part "SB_ON"))
    )
    (comp (ref "SB29")
      (value "SB_ON")
      (footprint "SOLDER-BRIDGE_R0603-0R")
      (description "Solder Bridge ON")
      (fields
        (field (name "INTERNAL_PART_NUMBER") "MCD-00071")
        (field (name "MANUFACTURER_PART_NUMBER") "RC0603JR-070RL")
        (field (name "PROVIDED_BY") "SUBCO")
      )
      (libsource (lib "MCD_PARTS_database") (part "SB_ON"))
    )
    (comp (ref "SB49")
      (value "SB_OFF")
      (footprint "SOLDER-BRIDGE_R0603-0R")
      (description "Solder Bridge OFF")
      (fields
        (field (name "INTERNAL_PART_NUMBER") "MCD-00072")
        (field (name "MANUFACTURER_PART_NUMBER") "RC0603JR-070RL")
        (field (name "PROVIDED_BY") "SUBCO")
      )
      (libsource (lib "MCD_PARTS_database") (part "SB_OFF"))
    )
    (comp (ref "SB50")
      (value "SB_OFF")
      (footprint "SOLDER-BRIDGE_R0603-0R")
      (description "Solder Bridge OFF")
      (fields
        (field (name "INTERNAL_PART_NUMBER") "MCD-00072")
        (field (name "MANUFACTURER_PART_NUMBER") "RC0603JR-070RL")
        (field (name "PROVIDED_BY") "SUBCO")
      )
      (libsource (lib "MCD_PARTS_database") (part "SB_OFF"))
    )
    (comp (ref "SB51")
      (value "SB_OFF")
      (footprint "SOLDER-BRIDGE_R0603-0R")
      (description "Solder Bridge OFF")
      (fields
        (field (name "INTERNAL_PART_NUMBER") "MCD-00072")
        (field (name "MANUFACTURER_PART_NUMBER") "RC0603JR-070RL")
        (field (name "PROVIDED_BY") "SUBCO")
      )
      (libsource (lib "MCD_PARTS_database") (part "SB_OFF"))
    )
    (comp (ref "SB52")
      (value "SB_OFF")
      (footprint "SOLDER-BRIDGE_R0603-0R")
      (description "Solder Bridge OFF")
      (fields
        (field (name "INTERNAL_PART_NUMBER") "MCD-00072")
        (field (name "MANUFACTURER_PART_NUMBER") "RC0603JR-070RL")
        (field (name "PROVIDED_BY") "SUBCO")
      )
      (libsource (lib "MCD_PARTS_database") (part "SB_OFF"))
    )
    (comp (ref "SB53")
      (value "SB_OFF")
      (footprint "SOLDER-BRIDGE_R0603-0R")
      (description "Solder Bridge OFF")
      (fields
        (field (name "INTERNAL_PART_NUMBER") "MCD-00072")
        (field (name "MANUFACTURER_PART_NUMBER") "RC0603JR-070RL")
        (field (name "PROVIDED_BY") "SUBCO")
      )
      (libsource (lib "MCD_PARTS_database") (part "SB_OFF"))
    )
    (comp (ref "SB54")
      (value "SB_OFF")
      (footprint "SOLDER-BRIDGE_R0603-0R")
      (description "Solder Bridge OFF")
      (fields
        (field (name "INTERNAL_PART_NUMBER") "MCD-00072")
        (field (name "MANUFACTURER_PART_NUMBER") "RC0603JR-070RL")
        (field (name "PROVIDED_BY") "SUBCO")
      )
      (libsource (lib "MCD_PARTS_database") (part "SB_OFF"))
    )
    (comp (ref "SB55")
      (value "SB_OFF")
      (footprint "SOLDER-BRIDGE_R0603-0R")
      (description "Solder Bridge OFF")
      (fields
        (field (name "INTERNAL_PART_NUMBER") "MCD-00072")
        (field (name "MANUFACTURER_PART_NUMBER") "RC0603JR-070RL")
        (field (name "PROVIDED_BY") "SUBCO")
      )
      (libsource (lib "MCD_PARTS_database") (part "SB_OFF"))
    )
    (comp (ref "SB56")
      (value "SB_OFF")
      (footprint "SOLDER-BRIDGE_R0603-0R")
      (description "Solder Bridge OFF")
      (fields
        (field (name "INTERNAL_PART_NUMBER") "MCD-00072")
        (field (name "MANUFACTURER_PART_NUMBER") "RC0603JR-070RL")
        (field (name "PROVIDED_BY") "SUBCO")
      )
      (libsource (lib "MCD_PARTS_database") (part "SB_OFF"))
    )
    (comp (ref "SB57")
      (value "SB_OFF")
      (footprint "SOLDER-BRIDGE_R0603-0R")
      (description "Solder Bridge OFF")
      (fields
        (field (name "INTERNAL_PART_NUMBER") "MCD-00072")
        (field (name "MANUFACTURER_PART_NUMBER") "RC0603JR-070RL")
        (field (name "PROVIDED_BY") "SUBCO")
      )
      (libsource (lib "MCD_PARTS_database") (part "SB_OFF"))
    )
    (comp (ref "SB58")
      (value "SB_OFF")
      (footprint "SOLDER-BRIDGE_R0603-0R")
      (description "Solder Bridge OFF")
      (fields
        (field (name "INTERNAL_PART_NUMBER") "MCD-00072")
        (field (name "MANUFACTURER_PART_NUMBER") "RC0603JR-070RL")
        (field (name "PROVIDED_BY") "SUBCO")
      )
      (libsource (lib "MCD_PARTS_database") (part "SB_OFF"))
    )
    (comp (ref "SB59")
      (value "SB_OFF")
      (footprint "SOLDER-BRIDGE_R0603-0R")
      (description "Solder Bridge OFF")
      (fields
        (field (name "INTERNAL_PART_NUMBER") "MCD-00072")
        (field (name "MANUFACTURER_PART_NUMBER") "RC0603JR-070RL")
        (field (name "PROVIDED_BY") "SUBCO")
      )
      (libsource (lib "MCD_PARTS_database") (part "SB_OFF"))
    )
    (comp (ref "SB60")
      (value "SB_OFF")
      (footprint "SOLDER-BRIDGE_R0603-0R")
      (description "Solder Bridge OFF")
      (fields
        (field (name "INTERNAL_PART_NUMBER") "MCD-00072")
        (field (name "MANUFACTURER_PART_NUMBER") "RC0603JR-070RL")
        (field (name "PROVIDED_BY") "SUBCO")
      )
      (libsource (lib "MCD_PARTS_database") (part "SB_OFF"))
    )
    (comp (ref "SB61")
      (value "SB_OFF")
      (footprint "SOLDER-BRIDGE_R0603-0R")
      (description "Solder Bridge OFF")
      (fields
        (field (name "INTERNAL_PART_NUMBER") "MCD-00072")
        (field (name "MANUFACTURER_PART_NUMBER") "RC0603JR-070RL")
        (field (name "PROVIDED_BY") "SUBCO")
      )
      (libsource (lib "MCD_PARTS_database") (part "SB_OFF"))
    )
    (comp (ref "SB62")
      (value "SB_OFF")
      (footprint "SOLDER-BRIDGE_R0603-0R")
      (description "Solder Bridge OFF")
      (fields
        (field (name "INTERNAL_PART_NUMBER") "MCD-00072")
        (field (name "MANUFACTURER_PART_NUMBER") "RC0603JR-070RL")
        (field (name "PROVIDED_BY") "SUBCO")
      )
      (libsource (lib "MCD_PARTS_database") (part "SB_OFF"))
    )
    (comp (ref "SB63")
      (value "SB_OFF")
      (footprint "SOLDER-BRIDGE_R0603-0R")
      (description "Solder Bridge OFF")
      (fields
        (field (name "INTERNAL_PART_NUMBER") "MCD-00072")
        (field (name "MANUFACTURER_PART_NUMBER") "RC0603JR-070RL")
        (field (name "PROVIDED_BY") "SUBCO")
      )
      (libsource (lib "MCD_PARTS_database") (part "SB_OFF"))
    )
    (comp (ref "SB64")
      (value "SB_OFF")
      (footprint "SOLDER-BRIDGE_R0603-0R")
      (description "Solder Bridge OFF")
      (fields
        (field (name "INTERNAL_PART_NUMBER") "MCD-00072")
        (field (name "MANUFACTURER_PART_NUMBER") "RC0603JR-070RL")
        (field (name "PROVIDED_BY") "SUBCO")
      )
      (libsource (lib "MCD_PARTS_database") (part "SB_OFF"))
    )
    (comp (ref "SB65")
      (value "SB_OFF")
      (footprint "SOLDER-BRIDGE_R0603-0R")
      (description "Solder Bridge OFF")
      (fields
        (field (name "INTERNAL_PART_NUMBER") "MCD-00072")
        (field (name "MANUFACTURER_PART_NUMBER") "RC0603JR-070RL")
        (field (name "PROVIDED_BY") "SUBCO")
      )
      (libsource (lib "MCD_PARTS_database") (part "SB_OFF"))
    )
    (comp (ref "SB66")
      (value "SB_OFF")
      (footprint "SOLDER-BRIDGE_R0603-0R")
      (description "Solder Bridge OFF")
      (fields
        (field (name "INTERNAL_PART_NUMBER") "MCD-00072")
        (field (name "MANUFACTURER_PART_NUMBER") "RC0603JR-070RL")
        (field (name "PROVIDED_BY") "SUBCO")
      )
      (libsource (lib "MCD_PARTS_database") (part "SB_OFF"))
    )
    (comp (ref "SB67")
      (value "SB_OFF")
      (footprint "SOLDER-BRIDGE_R0603-0R")
      (description "Solder Bridge OFF")
      (fields
        (field (name "INTERNAL_PART_NUMBER") "MCD-00072")
        (field (name "MANUFACTURER_PART_NUMBER") "RC0603JR-070RL")
        (field (name "PROVIDED_BY") "SUBCO")
      )
      (libsource (lib "MCD_PARTS_database") (part "SB_OFF"))
    )
    (comp (ref "SB68")
      (value "SB_OFF")
      (footprint "SOLDER-BRIDGE_R0603-0R")
      (description "Solder Bridge OFF")
      (fields
        (field (name "INTERNAL_PART_NUMBER") "MCD-00072")
        (field (name "MANUFACTURER_PART_NUMBER") "RC0603JR-070RL")
        (field (name "PROVIDED_BY") "SUBCO")
      )
      (libsource (lib "MCD_PARTS_database") (part "SB_OFF"))
    )
    (comp (ref "SB69")
      (value "SB_OFF")
      (footprint "SOLDER-BRIDGE_R0603-0R")
      (description "Solder Bridge OFF")
      (fields
        (field (name "INTERNAL_PART_NUMBER") "MCD-00072")
        (field (name "MANUFACTURER_PART_NUMBER") "RC0603JR-070RL")
        (field (name "PROVIDED_BY") "SUBCO")
      )
      (libsource (lib "MCD_PARTS_database") (part "SB_OFF"))
    )
    (comp (ref "SB70")
      (value "SB_OFF")
      (footprint "SOLDER-BRIDGE_R0603-0R")
      (description "Solder Bridge OFF")
      (fields
        (field (name "INTERNAL_PART_NUMBER") "MCD-00072")
        (field (name "MANUFACTURER_PART_NUMBER") "RC0603JR-070RL")
        (field (name "PROVIDED_BY") "SUBCO")
      )
      (libsource (lib "MCD_PARTS_database") (part "SB_OFF"))
    )
    (comp (ref "SB71")
      (value "SB_OFF")
      (footprint "SOLDER-BRIDGE_R0603-0R")
      (description "Solder Bridge OFF")
      (fields
        (field (name "INTERNAL_PART_NUMBER") "MCD-00072")
        (field (name "MANUFACTURER_PART_NUMBER") "RC0603JR-070RL")
        (field (name "PROVIDED_BY") "SUBCO")
      )
      (libsource (lib "MCD_PARTS_database") (part "SB_OFF"))
    )
    (comp (ref "SB72")
      (value "SB_OFF")
      (footprint "SOLDER-BRIDGE_R0603-0R")
      (description "Solder Bridge OFF")
      (fields
        (field (name "INTERNAL_PART_NUMBER") "MCD-00072")
        (field (name "MANUFACTURER_PART_NUMBER") "RC0603JR-070RL")
        (field (name "PROVIDED_BY") "SUBCO")
      )
      (libsource (lib "MCD_PARTS_database") (part "SB_OFF"))
    )
    (comp (ref "SB73")
      (value "SB_OFF")
      (footprint "SOLDER-BRIDGE_R0603-0R")
      (description "Solder Bridge OFF")
      (fields
        (field (name "INTERNAL_PART_NUMBER") "MCD-00072")
        (field (name "MANUFACTURER_PART_NUMBER") "RC0603JR-070RL")
        (field (name "PROVIDED_BY") "SUBCO")
      )
      (libsource (lib "MCD_PARTS_database") (part "SB_OFF"))
    )
    (comp (ref "SB74")
      (value "SB_OFF")
      (footprint "SOLDER-BRIDGE_R0603-0R")
      (description "Solder Bridge OFF")
      (fields
        (field (name "INTERNAL_PART_NUMBER") "MCD-00072")
        (field (name "MANUFACTURER_PART_NUMBER") "RC0603JR-070RL")
        (field (name "PROVIDED_BY") "SUBCO")
      )
      (libsource (lib "MCD_PARTS_database") (part "SB_OFF"))
    )
    (comp (ref "SB76")
      (value "SB_OFF")
      (footprint "SOLDER-BRIDGE_R0603-0R")
      (description "Solder Bridge OFF")
      (fields
        (field (name "INTERNAL_PART_NUMBER") "MCD-00072")
        (field (name "MANUFACTURER_PART_NUMBER") "RC0603JR-070RL")
        (field (name "PROVIDED_BY") "SUBCO")
      )
      (libsource (lib "MCD_PARTS_database") (part "SB_OFF"))
    )
    (comp (ref "SB77")
      (value "SB_OFF")
      (footprint "SOLDER-BRIDGE_R0603-0R")
      (description "Solder Bridge OFF")
      (fields
        (field (name "INTERNAL_PART_NUMBER") "MCD-00072")
        (field (name "MANUFACTURER_PART_NUMBER") "RC0603JR-070RL")
        (field (name "PROVIDED_BY") "SUBCO")
      )
      (libsource (lib "MCD_PARTS_database") (part "SB_OFF"))
    )
    (comp (ref "SB78")
      (value "SB_OFF")
      (footprint "SOLDER-BRIDGE_R0603-0R")
      (description "Solder Bridge OFF")
      (fields
        (field (name "INTERNAL_PART_NUMBER") "MCD-00072")
        (field (name "MANUFACTURER_PART_NUMBER") "RC0603JR-070RL")
        (field (name "PROVIDED_BY") "SUBCO")
      )
      (libsource (lib "MCD_PARTS_database") (part "SB_OFF"))
    )
    (comp (ref "SB79")
      (value "SB_OFF")
      (footprint "SOLDER-BRIDGE_R0603-0R")
      (description "Solder Bridge OFF")
      (fields
        (field (name "INTERNAL_PART_NUMBER") "MCD-00072")
        (field (name "MANUFACTURER_PART_NUMBER") "RC0603JR-070RL")
        (field (name "PROVIDED_BY") "SUBCO")
      )
      (libsource (lib "MCD_PARTS_database") (part "SB_OFF"))
    )
    (comp (ref "SB80")
      (value "SB_OFF")
      (footprint "SOLDER-BRIDGE_R0603-0R")
      (description "Solder Bridge OFF")
      (fields
        (field (name "INTERNAL_PART_NUMBER") "MCD-00072")
        (field (name "MANUFACTURER_PART_NUMBER") "RC0603JR-070RL")
        (field (name "PROVIDED_BY") "SUBCO")
      )
      (libsource (lib "MCD_PARTS_database") (part "SB_OFF"))
    )
    (comp (ref "SB83")
      (value "SB_OFF")
      (footprint "SOLDER-BRIDGE_R0603-0R")
      (description "Solder Bridge OFF")
      (fields
        (field (name "INTERNAL_PART_NUMBER") "MCD-00072")
        (field (name "MANUFACTURER_PART_NUMBER") "RC0603JR-070RL")
        (field (name "PROVIDED_BY") "SUBCO")
      )
      (libsource (lib "MCD_PARTS_database") (part "SB_OFF"))
    )
    (comp (ref "SB89")
      (value "SB_OFF")
      (footprint "SOLDER-BRIDGE_R0603-0R")
      (description "Solder Bridge OFF")
      (fields
        (field (name "INTERNAL_PART_NUMBER") "MCD-00072")
        (field (name "MANUFACTURER_PART_NUMBER") "RC0603JR-070RL")
        (field (name "PROVIDED_BY") "SUBCO")
      )
      (libsource (lib "MCD_PARTS_database") (part "SB_OFF"))
    )
    (comp (ref "SB91")
      (value "SB_OFF")
      (footprint "SOLDER-BRIDGE_R0603-0R")
      (description "Solder Bridge OFF")
      (fields
        (field (name "INTERNAL_PART_NUMBER") "MCD-00072")
        (field (name "MANUFACTURER_PART_NUMBER") "RC0603JR-070RL")
        (field (name "PROVIDED_BY") "SUBCO")
      )
      (libsource (lib "MCD_PARTS_database") (part "SB_OFF"))
    )
    (comp (ref "SB92")
      (value "SB_OFF")
      (footprint "SOLDER-BRIDGE_R0603-0R")
      (description "Solder Bridge OFF")
      (fields
        (field (name "INTERNAL_PART_NUMBER") "MCD-00072")
        (field (name "MANUFACTURER_PART_NUMBER") "RC0603JR-070RL")
        (field (name "PROVIDED_BY") "SUBCO")
      )
      (libsource (lib "MCD_PARTS_database") (part "SB_OFF"))
    )
    (comp (ref "SB93")
      (value "SB_OFF")
      (footprint "SOLDER-BRIDGE_R0603-0R")
      (description "Solder Bridge OFF")
      (fields
        (field (name "INTERNAL_PART_NUMBER") "MCD-00072")
        (field (name "MANUFACTURER_PART_NUMBER") "RC0603JR-070RL")
        (field (name "PROVIDED_BY") "SUBCO")
      )
      (libsource (lib "MCD_PARTS_database") (part "SB_OFF"))
    )
    (comp (ref "SB94")
      (value "SB_OFF")
      (footprint "SOLDER-BRIDGE_R0603-0R")
      (description "Solder Bridge OFF")
      (fields
        (field (name "INTERNAL_PART_NUMBER") "MCD-00072")
        (field (name "MANUFACTURER_PART_NUMBER") "RC0603JR-070RL")
        (field (name "PROVIDED_BY") "SUBCO")
      )
      (libsource (lib "MCD_PARTS_database") (part "SB_OFF"))
    )
    (comp (ref "SB95")
      (value "SB_OFF")
      (footprint "SOLDER-BRIDGE_R0603-0R")
      (description "Solder Bridge OFF")
      (fields
        (field (name "INTERNAL_PART_NUMBER") "MCD-00072")
        (field (name "MANUFACTURER_PART_NUMBER") "RC0603JR-070RL")
        (field (name "PROVIDED_BY") "SUBCO")
      )
      (libsource (lib "MCD_PARTS_database") (part "SB_OFF"))
    )
    (comp (ref "SB96")
      (value "SB_ON")
      (footprint "SOLDER-BRIDGE_R0603-0R")
      (description "Solder Bridge ON")
      (fields
        (field (name "INTERNAL_PART_NUMBER") "MCD-00071")
        (field (name "MANUFACTURER_PART_NUMBER") "RC0603JR-070RL")
        (field (name "PROVIDED_BY") "SUBCO")
      )
      (libsource (lib "MCD_PARTS_database") (part "SB_ON"))
    )
    (comp (ref "SB97")
      (value "SB_OFF")
      (footprint "SOLDER-BRIDGE_R0603-0R")
      (description "Solder Bridge OFF")
      (fields
        (field (name "INTERNAL_PART_NUMBER") "MCD-00072")
        (field (name "MANUFACTURER_PART_NUMBER") "RC0603JR-070RL")
        (field (name "PROVIDED_BY") "SUBCO")
      )
      (libsource (lib "MCD_PARTS_database") (part "SB_OFF"))
    )
    (comp (ref "SB98")
      (value "SB_OFF")
      (footprint "SOLDER-BRIDGE_R0603-0R")
      (description "Solder Bridge OFF")
      (fields
        (field (name "INTERNAL_PART_NUMBER") "MCD-00072")
        (field (name "MANUFACTURER_PART_NUMBER") "RC0603JR-070RL")
        (field (name "PROVIDED_BY") "SUBCO")
      )
      (libsource (lib "MCD_PARTS_database") (part "SB_OFF"))
    )
    (comp (ref "SB99")
      (value "SB_OFF")
      (footprint "SOLDER-BRIDGE_R0603-0R")
      (description "Solder Bridge OFF")
      (fields
        (field (name "INTERNAL_PART_NUMBER") "MCD-00072")
        (field (name "MANUFACTURER_PART_NUMBER") "RC0603JR-070RL")
        (field (name "PROVIDED_BY") "SUBCO")
      )
      (libsource (lib "MCD_PARTS_database") (part "SB_OFF"))
    )
    (comp (ref "SB100")
      (value "SB_OFF")
      (footprint "SOLDER-BRIDGE_R0603-0R")
      (description "Solder Bridge OFF")
      (fields
        (field (name "INTERNAL_PART_NUMBER") "MCD-00072")
        (field (name "MANUFACTURER_PART_NUMBER") "RC0603JR-070RL")
        (field (name "PROVIDED_BY") "SUBCO")
      )
      (libsource (lib "MCD_PARTS_database") (part "SB_OFF"))
    )
    (comp (ref "SB101")
      (value "SB_OFF")
      (footprint "SOLDER-BRIDGE_R0603-0R")
      (description "Solder Bridge OFF")
      (fields
        (field (name "INTERNAL_PART_NUMBER") "MCD-00072")
        (field (name "MANUFACTURER_PART_NUMBER") "RC0603JR-070RL")
        (field (name "PROVIDED_BY") "SUBCO")
      )
      (libsource (lib "MCD_PARTS_database") (part "SB_OFF"))
    )
    (comp (ref "SB103")
      (value "SB_OFF")
      (footprint "SOLDER-BRIDGE_R0603-0R")
      (description "Solder Bridge OFF")
      (fields
        (field (name "INTERNAL_PART_NUMBER") "MCD-00072")
        (field (name "MANUFACTURER_PART_NUMBER") "RC0603JR-070RL")
        (field (name "PROVIDED_BY") "SUBCO")
      )
      (libsource (lib "MCD_PARTS_database") (part "SB_OFF"))
    )
    (comp (ref "SB104")
      (value "SB_OFF")
      (footprint "SOLDER-BRIDGE_R0603-0R")
      (description "Solder Bridge OFF")
      (fields
        (field (name "INTERNAL_PART_NUMBER") "MCD-00072")
        (field (name "MANUFACTURER_PART_NUMBER") "RC0603JR-070RL")
        (field (name "PROVIDED_BY") "SUBCO")
      )
      (libsource (lib "MCD_PARTS_database") (part "SB_OFF"))
    )
    (comp (ref "SB105")
      (value "SB_OFF")
      (footprint "SOLDER-BRIDGE_R0603-0R")
      (description "Solder Bridge OFF")
      (fields
        (field (name "INTERNAL_PART_NUMBER") "MCD-00072")
        (field (name "MANUFACTURER_PART_NUMBER") "RC0603JR-070RL")
        (field (name "PROVIDED_BY") "SUBCO")
      )
      (libsource (lib "MCD_PARTS_database") (part "SB_OFF"))
    )
    (comp (ref "SB106")
      (value "SB_OFF")
      (footprint "SOLDER-BRIDGE_R0603-0R")
      (description "Solder Bridge OFF")
      (fields
        (field (name "INTERNAL_PART_NUMBER") "MCD-00072")
        (field (name "MANUFACTURER_PART_NUMBER") "RC0603JR-070RL")
        (field (name "PROVIDED_BY") "SUBCO")
      )
      (libsource (lib "MCD_PARTS_database") (part "SB_OFF"))
    )
    (comp (ref "SB107")
      (value "SB_ON")
      (footprint "SOLDER-BRIDGE_R0603-0R")
      (description "Solder Bridge ON")
      (fields
        (field (name "INTERNAL_PART_NUMBER") "MCD-00071")
        (field (name "MANUFACTURER_PART_NUMBER") "RC0603JR-070RL")
        (field (name "PROVIDED_BY") "SUBCO")
      )
      (libsource (lib "MCD_PARTS_database") (part "SB_ON"))
    )
    (comp (ref "SB108")
      (value "SB_OFF")
      (footprint "SOLDER-BRIDGE_R0603-0R")
      (description "Solder Bridge OFF")
      (fields
        (field (name "INTERNAL_PART_NUMBER") "MCD-00072")
        (field (name "MANUFACTURER_PART_NUMBER") "RC0603JR-070RL")
        (field (name "PROVIDED_BY") "SUBCO")
      )
      (libsource (lib "MCD_PARTS_database") (part "SB_OFF"))
    )
    (comp (ref "SB109")
      (value "SB_OFF")
      (footprint "SOLDER-BRIDGE_R0603-0R")
      (description "Solder Bridge OFF")
      (fields
        (field (name "INTERNAL_PART_NUMBER") "MCD-00072")
        (field (name "MANUFACTURER_PART_NUMBER") "RC0603JR-070RL")
        (field (name "PROVIDED_BY") "SUBCO")
      )
      (libsource (lib "MCD_PARTS_database") (part "SB_OFF"))
    )
    (comp (ref "SB110")
      (value "SB_ON")
      (footprint "SOLDER-BRIDGE_R0603-0R")
      (description "Solder Bridge ON")
      (fields
        (field (name "INTERNAL_PART_NUMBER") "MCD-00071")
        (field (name "MANUFACTURER_PART_NUMBER") "RC0603JR-070RL")
        (field (name "PROVIDED_BY") "SUBCO")
      )
      (libsource (lib "MCD_PARTS_database") (part "SB_ON"))
    )
    (comp (ref "SB111")
      (value "SB_ON")
      (footprint "SOLDER-BRIDGE_R0603-0R")
      (description "Solder Bridge ON")
      (fields
        (field (name "INTERNAL_PART_NUMBER") "MCD-00071")
        (field (name "MANUFACTURER_PART_NUMBER") "RC0603JR-070RL")
        (field (name "PROVIDED_BY") "SUBCO")
      )
      (libsource (lib "MCD_PARTS_database") (part "SB_ON"))
    )
    (comp (ref "SB112")
      (value "SB_OFF")
      (footprint "SOLDER-BRIDGE_R0603-0R")
      (description "Solder Bridge OFF")
      (fields
        (field (name "INTERNAL_PART_NUMBER") "MCD-00072")
        (field (name "MANUFACTURER_PART_NUMBER") "RC0603JR-070RL")
        (field (name "PROVIDED_BY") "SUBCO")
      )
      (libsource (lib "MCD_PARTS_database") (part "SB_OFF"))
    )
    (comp (ref "SB113")
      (value "SB_OFF")
      (footprint "SOLDER-BRIDGE_R0603-0R")
      (description "Solder Bridge OFF")
      (fields
        (field (name "INTERNAL_PART_NUMBER") "MCD-00072")
        (field (name "MANUFACTURER_PART_NUMBER") "RC0603JR-070RL")
        (field (name "PROVIDED_BY") "SUBCO")
      )
      (libsource (lib "MCD_PARTS_database") (part "SB_OFF"))
    )
    (comp (ref "SB114")
      (value "SB_OFF")
      (footprint "SOLDER-BRIDGE_R0603-0R")
      (description "Solder Bridge OFF")
      (fields
        (field (name "INTERNAL_PART_NUMBER") "MCD-00072")
        (field (name "MANUFACTURER_PART_NUMBER") "RC0603JR-070RL")
        (field (name "PROVIDED_BY") "SUBCO")
      )
      (libsource (lib "MCD_PARTS_database") (part "SB_OFF"))
    )
    (comp (ref "SB115")
      (value "SB_OFF")
      (footprint "SOLDER-BRIDGE_R0603-0R")
      (description "Solder Bridge OFF")
      (fields
        (field (name "INTERNAL_PART_NUMBER") "MCD-00072")
        (field (name "MANUFACTURER_PART_NUMBER") "RC0603JR-070RL")
        (field (name "PROVIDED_BY") "SUBCO")
      )
      (libsource (lib "MCD_PARTS_database") (part "SB_OFF"))
    )
    (comp (ref "SB116")
      (value "SB_OFF")
      (footprint "SOLDER-BRIDGE_R0603-0R")
      (description "Solder Bridge OFF")
      (fields
        (field (name "INTERNAL_PART_NUMBER") "MCD-00072")
        (field (name "MANUFACTURER_PART_NUMBER") "RC0603JR-070RL")
        (field (name "PROVIDED_BY") "SUBCO")
      )
      (libsource (lib "MCD_PARTS_database") (part "SB_OFF"))
    )
    (comp (ref "SB117")
      (value "SB_OFF")
      (footprint "SOLDER-BRIDGE_R0603-0R")
      (description "Solder Bridge OFF")
      (fields
        (field (name "INTERNAL_PART_NUMBER") "MCD-00072")
        (field (name "MANUFACTURER_PART_NUMBER") "RC0603JR-070RL")
        (field (name "PROVIDED_BY") "SUBCO")
      )
      (libsource (lib "MCD_PARTS_database") (part "SB_OFF"))
    )
    (comp (ref "SB118")
      (value "SB_OFF")
      (footprint "SOLDER-BRIDGE_R0603-0R")
      (description "Solder Bridge OFF")
      (fields
        (field (name "INTERNAL_PART_NUMBER") "MCD-00072")
        (field (name "MANUFACTURER_PART_NUMBER") "RC0603JR-070RL")
        (field (name "PROVIDED_BY") "SUBCO")
      )
      (libsource (lib "MCD_PARTS_database") (part "SB_OFF"))
    )
    (comp (ref "SB123")
      (value "SB_ON")
      (footprint "SOLDER-BRIDGE_R0603-0R")
      (description "Solder Bridge ON")
      (fields
        (field (name "INTERNAL_PART_NUMBER") "MCD-00071")
        (field (name "MANUFACTURER_PART_NUMBER") "RC0603JR-070RL")
        (field (name "PROVIDED_BY") "SUBCO")
      )
      (libsource (lib "MCD_PARTS_database") (part "SB_ON"))
    )
    (comp (ref "U6")
      (value "STM32G474QET6U")
      (footprint "ICC_LQFP128_14X14_P040")
      (fields
        (field (name "INTERNAL_PART_NUMBER") "MCD-01707")
        (field (name "MANUFACTURER") "STMICROELECTRONICS")
        (field (name "PROVIDED_BY") "SUBCO with ST control")
      )
      (libsource (lib "MCD_PARTS_database") (part "STM32G474WET6"))
    )
  )
  (nets
    (net (code "18") (name "/ADC_OUTN") (class "Default")
      (node (ref "SB27") (pin "1") (pinfunction "1_1") (pintype "passive"))
    )
    (net (code "19") (name "/ADC_OUTP") (class "Default")
      (node (ref "SB116") (pin "2") (pinfunction "2_2") (pintype "passive"))
    )
    (net (code "20") (name "/Audio_INT") (class "Default")
      (node (ref "R43") (pin "2") (pinfunction "2_2") (pintype "passive"))
    )
    (net (code "21") (name "/BK_Drive") (class "Default")
      (node (ref "R26") (pin "1") (pinfunction "1_1") (pintype "passive"))
    )
    (net (code "22") (name "/BK_Sense") (class "Default")
      (node (ref "SB10") (pin "2") (pinfunction "2_2") (pintype "passive"))
    )
    (net (code "23") (name "/BOOT0") (class "Default")
      (node (ref "R123") (pin "1") (pinfunction "1_1") (pintype "passive"))
    )
    (net (code "24") (name "/CMOP6_OUT") (class "Default")
      (node (ref "SB9") (pin "1") (pinfunction "1_1") (pintype "passive"))
    )
    (net (code "25") (name "/DAC") (class "Default")
      (node (ref "SB25") (pin "1") (pinfunction "1_1") (pintype "passive"))
    )
    (net (code "26") (name "/DISCHARGE") (class "Default")
      (node (ref "SB18") (pin "2") (pinfunction "2_2") (pintype "passive"))
    )
    (net (code "27") (name "/FDCAN1_RX") (class "Default")
      (node (ref "JP1") (pin "2") (pinfunction "NO_2") (pintype "passive"))
    )
    (net (code "28") (name "/FDCAN1_TX") (class "Default")
      (node (ref "R127") (pin "2") (pinfunction "2_2") (pintype "passive"))
    )
    (net (code "29") (name "/FDCAN2_RX") (class "Default")
      (node (ref "R112") (pin "2") (pinfunction "2_2") (pintype "passive"))
    )
    (net (code "30") (name "/FDCAN2_TX") (class "Default")
      (node (ref "SB5") (pin "2") (pinfunction "2_2") (pintype "passive"))
    )
    (net (code "31") (name "/FMC_A0") (class "Default")
      (node (ref "R136") (pin "2") (pinfunction "2_2") (pintype "passive"))
    )
    (net (code "32") (name "/FMC_A1") (class "Default")
      (node (ref "R138") (pin "2") (pinfunction "2_2") (pintype "passive"))
    )
    (net (code "33") (name "/FMC_A2") (class "Default")
      (node (ref "R132") (pin "2") (pinfunction "2_2") (pintype "passive"))
    )
    (net (code "34") (name "/FMC_A3") (class "Default")
      (node (ref "R139") (pin "2") (pinfunction "2_2") (pintype "passive"))
    )
    (net (code "35") (name "/FMC_A4") (class "Default")
      (node (ref "R140") (pin "2") (pinfunction "2_2") (pintype "passive"))
    )
    (net (code "36") (name "/FMC_A5") (class "Default")
      (node (ref "R137") (pin "2") (pinfunction "2_2") (pintype "passive"))
    )
    (net (code "37") (name "/FMC_A6") (class "Default")
      (node (ref "R93") (pin "2") (pinfunction "2_2") (pintype "passive"))
    )
    (net (code "38") (name "/FMC_A7") (class "Default")
      (node (ref "R89") (pin "2") (pinfunction "2_2") (pintype "passive"))
    )
    (net (code "39") (name "/FMC_A8") (class "Default")
      (node (ref "R88") (pin "2") (pinfunction "2_2") (pintype "passive"))
    )
    (net (code "40") (name "/FMC_A9") (class "Default")
      (node (ref "R87") (pin "2") (pinfunction "2_2") (pintype "passive"))
    )
    (net (code "41") (name "/FMC_A10") (class "Default")
      (node (ref "R48") (pin "2") (pinfunction "2_2") (pintype "passive"))
    )
    (net (code "42") (name "/FMC_A11") (class "Default")
      (node (ref "R28") (pin "2") (pinfunction "2_2") (pintype "passive"))
    )
    (net (code "43") (name "/FMC_A12") (class "Default")
      (node (ref "R50") (pin "2") (pinfunction "2_2") (pintype "passive"))
    )
    (net (code "44") (name "/FMC_A13") (class "Default")
      (node (ref "R27") (pin "2") (pinfunction "2_2") (pintype "passive"))
    )
    (net (code "45") (name "/FMC_A14") (class "Default")
      (node (ref "R53") (pin "2") (pinfunction "2_2") (pintype "passive"))
    )
    (net (code "46") (name "/FMC_A15") (class "Default")
      (node (ref "R68") (pin "2") (pinfunction "2_2") (pintype "passive"))
    )
    (net (code "47") (name "/FMC_A16") (class "Default")
      (node (ref "R39") (pin "2") (pinfunction "2_2") (pintype "passive"))
    )
    (net (code "48") (name "/FMC_A17") (class "Default")
      (node (ref "R42") (pin "2") (pinfunction "2_2") (pintype "passive"))
    )
    (net (code "49") (name "/FMC_A18") (class "Default")
      (node (ref "R41") (pin "2") (pinfunction "2_2") (pintype "passive"))
    )
    (net (code "50") (name "/FMC_A19") (class "Default")
      (node (ref "R146") (pin "1") (pinfunction "1_1") (pintype "passive"))
    )
    (net (code "51") (name "/FMC_A20") (class "Default")
      (node (ref "R143") (pin "1") (pinfunction "1_1") (pintype "passive"))
    )
    (net (code "53") (name "/FMC_D0") (class "Default")
      (node (ref "R29") (pin "2") (pinfunction "2_2") (pintype "passive"))
    )
    (net (code "54") (name "/FMC_D1") (class "Default")
      (node (ref "R40") (pin "2") (pinfunction "2_2") (pintype "passive"))
    )
    (net (code "55") (name "/FMC_D2") (class "Default")
      (node (ref "R83") (pin "2") (pinfunction "2_2") (pintype "passive"))
    )
    (net (code "56") (name "/FMC_D3") (class "Default")
      (node (ref "R85") (pin "2") (pinfunction "2_2") (pintype "passive"))
    )
    (net (code "57") (name "/FMC_D4") (class "Default")
      (node (ref "R84") (pin "1") (pinfunction "1_1") (pintype "passive"))
    )
    (net (code "58") (name "/FMC_D5") (class "Default")
      (node (ref "R82") (pin "1") (pinfunction "1_1") (pintype "passive"))
    )
    (net (code "59") (name "/FMC_D6") (class "Default")
      (node (ref "R79") (pin "1") (pinfunction "1_1") (pintype "passive"))
    )
    (net (code "60") (name "/FMC_D7") (class "Default")
      (node (ref "R75") (pin "1") (pinfunction "1_1") (pintype "passive"))
    )
    (net (code "61") (name "/FMC_D8") (class "Default")
      (node (ref "R71") (pin "1") (pinfunction "1_1") (pintype "passive"))
    )
    (net (code "62") (name "/FMC_D9") (class "Default")
      (node (ref "R69") (pin "1") (pinfunction "1_1") (pintype "passive"))
    )
    (net (code "63") (name "/FMC_D10") (class "Default")
      (node (ref "R63") (pin "1") (pinfunction "1_1") (pintype "passive"))
    )
    (net (code "64") (name "/FMC_D11") (class "Default")
      (node (ref "R62") (pin "1") (pinfunction "1_1") (pintype "passive"))
    )
    (net (code "65") (name "/FMC_D12") (class "Default")
      (node (ref "R60") (pin "1") (pinfunction "1_1") (pintype "passive"))
    )
    (net (code "66") (name "/FMC_D13") (class "Default")
      (node (ref "R34") (pin "2") (pinfunction "2_2") (pintype "passive"))
    )
    (net (code "67") (name "/FMC_D14") (class "Default")
      (node (ref "R37") (pin "2") (pinfunction "2_2") (pintype "passive"))
    )
    (net (code "68") (name "/FMC_D15") (class "Default")
      (node (ref "R38") (pin "2") (pinfunction "2_2") (pintype "passive"))
    )
    (net (code "70") (name "/FMC_NBL0") (class "Default")
      (node (ref "R148") (pin "1") (pinfunction "1_1") (pintype "passive"))
    )
    (net (code "71") (name "/FMC_NBL1") (class "Default")
      (node (ref "R149") (pin "1") (pinfunction "1_1") (pintype "passive"))
    )
    (net (code "72") (name "/FMC_NE1") (class "Default")
      (node (ref "R101") (pin "2") (pinfunction "2_2") (pintype "passive"))
    )
    (net (code "73") (name "/FMC_NOE") (class "Default")
      (node (ref "R94") (pin "2") (pinfunction "2_2") (pintype "passive"))
    )
    (net (code "74") (name "/FMC_NWE") (class "Default")
      (node (ref "R97") (pin "2") (pinfunction "2_2") (pintype "passive"))
    )
    (net (code "75") (name "/I2C3_SCL") (class "Default")
      (node (ref "R73") (pin "1") (pinfunction "1_1") (pintype "passive"))
      (node (ref "R74") (pin "2") (pinfunction "2_2") (pintype "passive"))
    )
    (net (code "76") (name "/I2C3_SDA") (class "Default")
      (node (ref "R78") (pin "2") (pinfunction "2_2") (pintype "passive"))
      (node (ref "R80") (pin "1") (pinfunction "1_1") (pintype "passive"))
    )
    (net (code "77") (name "/I2C3_SMBA") (class "Default")
      (node (ref "R70") (pin "2") (pinfunction "2_2") (pintype "passive"))
    )
    (net (code "78") (name "/JTCK-SWCLK") (class "Default")
      (node (ref "R47") (pin "1") (pinfunction "1_1") (pintype "passive"))
    )
    (net (code "79") (name "/JTDI") (class "Default")
      (node (ref "R54") (pin "1") (pinfunction "1_1") (pintype "passive"))
    )
    (net (code "80") (name "/JTDO-SWO") (class "Default")
      (node (ref "R107") (pin "2") (pinfunction "2_2") (pintype "passive"))
    )
    (net (code "81") (name "/JTMS-SWDIO") (class "Default")
      (node (ref "R44") (pin "1") (pinfunction "1_1") (pintype "passive"))
    )
    (net (code "82") (name "/JTRST") (class "Default")
      (node (ref "R109") (pin "1") (pinfunction "1_1") (pintype "passive"))
    )
    (net (code "83") (name "/LCD_CS") (class "Default")
      (node (ref "R49") (pin "1") (pinfunction "1_1") (pintype "passive"))
    )
    (net (code "84") (name "/LED1") (class "Default")
      (node (ref "R81") (pin "2") (pinfunction "2_2") (pintype "passive"))
    )
    (net (code "85") (name "/LED3") (class "Default")
      (node (ref "R96") (pin "2") (pinfunction "2_2") (pintype "passive"))
    )
    (net (code "86") (name "/MC1_Ain") (class "Default")
      (node (ref "SB113") (pin "1") (pinfunction "1_1") (pintype "passive"))
    )
    (net (code "87") (name "/MC1_Bin") (class "Default")
      (node (ref "SB114") (pin "1") (pinfunction "1_1") (pintype "passive"))
    )
    (net (code "88") (name "/MC1_BusVoltage") (class "Default")
      (node (ref "SB115") (pin "1") (pinfunction "1_1") (pintype "passive"))
    )
    (net (code "89") (name "/MC1_Cin") (class "Default")
      (node (ref "SB99") (pin "1") (pinfunction "1_1") (pintype "passive"))
    )
    (net (code "90") (name "/MC1_DissipativeBrake") (class "Default")
      (node (ref "SB97") (pin "1") (pinfunction "1_1") (pintype "passive"))
    )
    (net (code "91") (name "/MC1_EnA") (class "Default")
      (node (ref "SB98") (pin "1") (pinfunction "1_1") (pintype "passive"))
    )
    (net (code "92") (name "/MC1_EnB") (class "Default")
      (node (ref "SB89") (pin "1") (pinfunction "1_1") (pintype "passive"))
    )
    (net (code "93") (name "/MC1_EnIndex") (class "Default")
      (node (ref "SB62") (pin "1") (pinfunction "1_1") (pintype "passive"))
      (node (ref "SB92") (pin "1") (pinfunction "1_1") (pintype "passive"))
    )
    (net (code "94") (name "/MC1_ICL_SHUTOUT") (class "Default")
      (node (ref "SB109") (pin "1") (pinfunction "1_1") (pintype "passive"))
    )
    (net (code "95") (name "/MC1_MC2_PFC_Ind") (class "Default")
      (node (ref "SB55") (pin "1") (pinfunction "1_1") (pintype "passive"))
    )
    (net (code "96") (name "/MC1_MC2_PFC_SD") (class "Default")
      (node (ref "SB17") (pin "1") (pinfunction "1_1") (pintype "passive"))
    )
    (net (code "97") (name "/MC1_MC2_PFC_Vac") (class "Default")
      (node (ref "SB56") (pin "1") (pinfunction "1_1") (pintype "passive"))
    )
    (net (code "98") (name "/MC1_MC2_PFCpwm") (class "Default")
      (node (ref "SB118") (pin "1") (pinfunction "1_1") (pintype "passive"))
    )
    (net (code "99") (name "/MC1_MC2_PFCsync") (class "Default")
      (node (ref "SB103") (pin "1") (pinfunction "1_1") (pintype "passive"))
    )
    (net (code "100") (name "/MC1_PWM_1H") (class "Default")
      (node (ref "SB78") (pin "1") (pinfunction "1_1") (pintype "passive"))
    )
    (net (code "101") (name "/MC1_PWM_1L") (class "Default")
      (node (ref "SB79") (pin "1") (pinfunction "1_1") (pintype "passive"))
    )
    (net (code "102") (name "/MC1_PWM_2H") (class "Default")
      (node (ref "SB76") (pin "1") (pinfunction "1_1") (pintype "passive"))
    )
    (net (code "103") (name "/MC1_PWM_2L") (class "Default")
      (node (ref "SB77") (pin "1") (pinfunction "1_1") (pintype "passive"))
    )
    (net (code "104") (name "/MC1_PWM_3H") (class "Default")
      (node (ref "SB73") (pin "1") (pinfunction "1_1") (pintype "passive"))
    )
    (net (code "105") (name "/MC1_PWM_3L") (class "Default")
      (node (ref "SB74") (pin "1") (pinfunction "1_1") (pintype "passive"))
    )
    (net (code "106") (name "/MC1_STOP") (class "Default")
      (node (ref "SB69") (pin "1") (pinfunction "1_1") (pintype "passive"))
    )
    (net (code "107") (name "/MC1_Temp") (class "Default")
      (node (ref "SB100") (pin "1") (pinfunction "1_1") (pintype "passive"))
    )
    (net (code "108") (name "/MC2_Ain") (class "Default")
      (node (ref "SB60") (pin "1") (pinfunction "1_1") (pintype "passive"))
    )
    (net (code "109") (name "/MC2_Bin") (class "Default")
      (node (ref "SB59") (pin "1") (pinfunction "1_1") (pintype "passive"))
    )
    (net (code "110") (name "/MC2_BusVoltage") (class "Default")
      (node (ref "SB72") (pin "1") (pinfunction "1_1") (pintype "passive"))
    )
    (net (code "111") (name "/MC2_Cin") (class "Default")
      (node (ref "SB57") (pin "1") (pinfunction "1_1") (pintype "passive"))
    )
    (net (code "112") (name "/MC2_DissipativeBrake") (class "Default")
      (node (ref "SB112") (pin "1") (pinfunction "1_1") (pintype "passive"))
    )
    (net (code "113") (name "/MC2_EnA") (class "Default")
      (node (ref "SB52") (pin "1") (pinfunction "1_1") (pintype "passive"))
    )
    (net (code "114") (name "/MC2_EnB") (class "Default")
      (node (ref "SB108") (pin "1") (pinfunction "1_1") (pintype "passive"))
    )
    (net (code "115") (name "/MC2_EnIndex") (class "Default")
      (node (ref "SB106") (pin "1") (pinfunction "1_1") (pintype "passive"))
      (node (ref "SB58") (pin "1") (pinfunction "1_1") (pintype "passive"))
    )
    (net (code "116") (name "/MC2_ICL_SHUTOUT") (class "Default")
      (node (ref "SB61") (pin "1") (pinfunction "1_1") (pintype "passive"))
    )
    (net (code "117") (name "/MC2_PWM_1H") (class "Default")
      (node (ref "SB49") (pin "1") (pinfunction "1_1") (pintype "passive"))
    )
    (net (code "118") (name "/MC2_PWM_1L") (class "Default")
      (node (ref "SB64") (pin "1") (pinfunction "1_1") (pintype "passive"))
    )
    (net (code "119") (name "/MC2_PWM_2H") (class "Default")
      (node (ref "SB50") (pin "1") (pinfunction "1_1") (pintype "passive"))
    )
    (net (code "120") (name "/MC2_PWM_2L") (class "Default")
      (node (ref "SB68") (pin "1") (pinfunction "1_1") (pintype "passive"))
    )
    (net (code "121") (name "/MC2_PWM_3H") (class "Default")
      (node (ref "SB51") (pin "1") (pinfunction "1_1") (pintype "passive"))
    )
    (net (code "122") (name "/MC2_PWM_3L") (class "Default")
      (node (ref "SB66") (pin "1") (pinfunction "1_1") (pintype "passive"))
    )
    (net (code "123") (name "/MC2_STOP") (class "Default")
      (node (ref "SB23") (pin "1") (pinfunction "1_1") (pintype "passive"))
    )
    (net (code "124") (name "/MC2_Temp") (class "Default")
      (node (ref "SB83") (pin "1") (pinfunction "1_1") (pintype "passive"))
    )
    (net (code "125") (name "/MC_DAC_OUT1") (class "Default")
      (node (ref "SB93") (pin "1") (pinfunction "1_1") (pintype "passive"))
    )
    (net (code "126") (name "/MC_DAC_OUT2") (class "Default")
      (node (ref "SB24") (pin "1") (pinfunction "1_1") (pintype "passive"))
    )
    (net (code "127") (name "/MFX_IRQ_OUT") (class "Default")
      (node (ref "SB26") (pin "1") (pinfunction "1_1") (pintype "passive"))
    )
    (net (code "128") (name "/MFX_WAKEUP") (class "Default")
      (node (ref "SB6") (pin "1") (pinfunction "1_1") (pintype "passive"))
    )
    (net (code "129") (name "/NRST") (class "Default")
      (node (ref "U6") (pin "21") (pinfunction "PG10-NRST_21") (pintype "passive"))
    )
    (net (code "130") (name "/OPAMP1_INN") (class "Default")
      (node (ref "SB105") (pin "1") (pinfunction "1_1") (pintype "passive"))
    )
    (net (code "131") (name "/OPAMP1_INP") (class "Default")
      (node (ref "SB95") (pin "1") (pinfunction "1_1") (pintype "passive"))
    )
    (net (code "132") (name "/OPAMP1_OUT") (class "Default")
      (node (ref "SB117") (pin "1") (pinfunction "1_1") (pintype "passive"))
    )
    (net (code "133") (name "/OPAMP2_IN1P") (class "Default")
      (node (ref "SB101") (pin "1") (pinfunction "1_1") (pintype "passive"))
    )
    (net (code "134") (name "/OPAMP2_IN2P") (class "Default")
      (node (ref "SB70") (pin "1") (pinfunction "1_1") (pintype "passive"))
    )
    (net (code "135") (name "/OPAMP2_INN") (class "Default")
      (node (ref "SB20") (pin "1") (pinfunction "1_1") (pintype "passive"))
    )
    (net (code "136") (name "/OPAMP2_OUT") (class "Default")
      (node (ref "SB104") (pin "1") (pinfunction "1_1") (pintype "passive"))
    )
    (net (code "137") (name "/OPAMP3_INN") (class "Default")
      (node (ref "SB80") (pin "1") (pinfunction "1_1") (pintype "passive"))
    )
    (net (code "138") (name "/OPAMP3_INP") (class "Default")
      (node (ref "SB94") (pin "1") (pinfunction "1_1") (pintype "passive"))
    )
    (net (code "139") (name "/OPAMP3_OUT") (class "Default")
      (node (ref "SB91") (pin "1") (pinfunction "1_1") (pintype "passive"))
    )
    (net (code "140") (name "/OPAMP4_IN1P") (class "Default")
      (node (ref "SB67") (pin "1") (pinfunction "1_1") (pintype "passive"))
    )
    (net (code "141") (name "/OPAMP4_IN2P") (class "Default")
      (node (ref "SB63") (pin "1") (pinfunction "1_1") (pintype "passive"))
    )
    (net (code "142") (name "/OPAMP4_INN") (class "Default")
      (node (ref "SB71") (pin "1") (pinfunction "1_1") (pintype "passive"))
    )
    (net (code "143") (name "/OPAMP4_OUT") (class "Default")
      (node (ref "SB65") (pin "1") (pinfunction "1_1") (pintype "passive"))
    )
    (net (code "144") (name "/OPAMP4_VINM") (class "Default")
      (node (ref "SB11") (pin "2") (pinfunction "2_2") (pintype "passive"))
    )
    (net (code "145") (name "/OPAMP4_VOUT") (class "Default")
      (node (ref "SB7") (pin "2") (pinfunction "2_2") (pintype "passive"))
    )
    (net (code "146") (name "/OPAMP4{slash}COMP6_INP") (class "Default")
      (node (ref "SB8") (pin "2") (pinfunction "2_2") (pintype "passive"))
    )
    (net (code "147") (name "/PA0") (class "Default")
      (node (ref "SB116") (pin "1") (pinfunction "1_1") (pintype "passive"))
      (node (ref "SB26") (pin "2") (pinfunction "2_2") (pintype "passive"))
      (node (ref "SB98") (pin "2") (pinfunction "2_2") (pintype "passive"))
      (node (ref "U6") (pin "27") (pinfunction "PA0_27") (pintype "passive"))
    )
    (net (code "148") (name "/PA1") (class "Default")
      (node (ref "SB27") (pin "2") (pinfunction "2_2") (pintype "passive"))
      (node (ref "SB95") (pin "2") (pinfunction "2_2") (pintype "passive"))
      (node (ref "U6") (pin "28") (pinfunction "PA1_28") (pintype "passive"))
    )
    (net (code "149") (name "/PA2") (class "Default")
      (node (ref "R150") (pin "2") (pinfunction "2_2") (pintype "passive"))
      (node (ref "SB117") (pin "2") (pinfunction "2_2") (pintype "passive"))
      (node (ref "U6") (pin "29") (pinfunction "PA2_29") (pintype "passive"))
    )
    (net (code "150") (name "/PA3") (class "Default")
      (node (ref "R129") (pin "2") (pinfunction "2_2") (pintype "passive"))
      (node (ref "SB105") (pin "2") (pinfunction "2_2") (pintype "passive"))
      (node (ref "U6") (pin "32") (pinfunction "PA3_32") (pintype "passive"))
    )
    (net (code "151") (name "/PA4") (class "Default")
      (node (ref "SB25") (pin "2") (pinfunction "2_2") (pintype "passive"))
      (node (ref "SB93") (pin "2") (pinfunction "2_2") (pintype "passive"))
      (node (ref "U6") (pin "33") (pinfunction "PA4_33") (pintype "passive"))
    )
    (net (code "152") (name "/PA5") (class "Default")
      (node (ref "SB24") (pin "2") (pinfunction "2_2") (pintype "passive"))
      (node (ref "U6") (pin "34") (pinfunction "PA5_34") (pintype "passive"))
    )
    (net (code "153") (name "/PA6") (class "Default")
      (node (ref "R121") (pin "2") (pinfunction "2_2") (pintype "passive"))
      (node (ref "SB104") (pin "2") (pinfunction "2_2") (pintype "passive"))
      (node (ref "U6") (pin "35") (pinfunction "PA6_35") (pintype "passive"))
    )
    (net (code "154") (name "/PA7") (class "Default")
      (node (ref "R118") (pin "2") (pinfunction "2_2") (pintype "passive"))
      (node (ref "SB101") (pin "2") (pinfunction "2_2") (pintype "passive"))
      (node (ref "U6") (pin "36") (pinfunction "PA7_36") (pintype "passive"))
    )
    (net (code "155") (name "/PA8") (class "Default")
      (node (ref "R30") (pin "2") (pinfunction "2_2") (pintype "passive"))
      (node (ref "U6") (pin "89") (pinfunction "PA8_89") (pintype "passive"))
    )
    (net (code "156") (name "/PA9") (class "Default")
      (node (ref "SB4") (pin "2") (pinfunction "2_2") (pintype "passive"))
      (node (ref "SB54") (pin "2") (pinfunction "2_2") (pintype "passive"))
      (node (ref "U6") (pin "90") (pinfunction "PA9_90") (pintype "passive"))
    )
    (net (code "157") (name "/PA10") (class "Default")
      (node (ref "SB3") (pin "2") (pinfunction "2_2") (pintype "passive"))
      (node (ref "SB53") (pin "2") (pinfunction "2_2") (pintype "passive"))
      (node (ref "U6") (pin "91") (pinfunction "PA10_91") (pintype "passive"))
    )
    (net (code "158") (name "/PA11") (class "Default")
      (node (ref "R46") (pin "2") (pinfunction "2_2") (pintype "passive"))
      (node (ref "U6") (pin "92") (pinfunction "PA11_92") (pintype "passive"))
    )
    (net (code "159") (name "/PA12") (class "Default")
      (node (ref "R45") (pin "2") (pinfunction "2_2") (pintype "passive"))
      (node (ref "U6") (pin "93") (pinfunction "PA12_93") (pintype "passive"))
    )
    (net (code "160") (name "/PA13") (class "Default")
      (node (ref "R44") (pin "2") (pinfunction "2_2") (pintype "passive"))
      (node (ref "U6") (pin "96") (pinfunction "PA13_96") (pintype "passive"))
    )
    (net (code "161") (name "/PA14") (class "Default")
      (node (ref "R47") (pin "2") (pinfunction "2_2") (pintype "passive"))
      (node (ref "U6") (pin "98") (pinfunction "PA14_98") (pintype "passive"))
    )
    (net (code "162") (name "/PA15") (class "Default")
      (node (ref "R54") (pin "2") (pinfunction "2_2") (pintype "passive"))
      (node (ref "SB62") (pin "2") (pinfunction "2_2") (pintype "passive"))
      (node (ref "U6") (pin "99") (pinfunction "PA15_99") (pintype "passive"))
    )
    (net (code "164") (name "/PB0") (class "Default")
      (node (ref "R108") (pin "1") (pinfunction "1_1") (pintype "passive"))
      (node (ref "SB94") (pin "2") (pinfunction "2_2") (pintype "passive"))
      (node (ref "U6") (pin "39") (pinfunction "PB0_39") (pintype "passive"))
    )
    (net (code "165") (name "/PB1") (class "Default")
      (node (ref "R102") (pin "1") (pinfunction "1_1") (pintype "passive"))
      (node (ref "SB91") (pin "2") (pinfunction "2_2") (pintype "passive"))
      (node (ref "U6") (pin "40") (pinfunction "PB1_40") (pintype "passive"))
    )
    (net (code "166") (name "/PB2") (class "Default")
      (node (ref "SB18") (pin "1") (pinfunction "1_1") (pintype "passive"))
      (node (ref "SB80") (pin "2") (pinfunction "2_2") (pintype "passive"))
      (node (ref "U6") (pin "41") (pinfunction "PB2_41") (pintype "passive"))
    )
    (net (code "167") (name "/PB3") (class "Default")
      (node (ref "R107") (pin "1") (pinfunction "1_1") (pintype "passive"))
      (node (ref "U6") (pin "118") (pinfunction "PB3_118") (pintype "passive"))
    )
    (net (code "168") (name "/PB4") (class "Default")
      (node (ref "R109") (pin "2") (pinfunction "2_2") (pintype "passive"))
      (node (ref "SB96") (pin "1") (pinfunction "1_1") (pintype "passive"))
      (node (ref "U6") (pin "119") (pinfunction "PB4_119") (pintype "passive"))
    )
    (net (code "169") (name "/PB5") (class "Default")
      (node (ref "R112") (pin "1") (pinfunction "1_1") (pintype "passive"))
      (node (ref "U6") (pin "120") (pinfunction "PB5_120") (pintype "passive"))
    )
    (net (code "170") (name "/PB6") (class "Default")
      (node (ref "SB21") (pin "1") (pinfunction "1_1") (pintype "passive"))
      (node (ref "U6") (pin "121") (pinfunction "PB6_121") (pintype "passive"))
    )
    (net (code "171") (name "/PB7") (class "Default")
      (node (ref "SB23") (pin "2") (pinfunction "2_2") (pintype "passive"))
      (node (ref "U6") (pin "122") (pinfunction "PB7_122") (pintype "passive"))
    )
    (net (code "172") (name "/PB8") (class "Default")
      (node (ref "JP1") (pin "1") (pinfunction "COMMON_1") (pintype "passive"))
      (node (ref "R123") (pin "2") (pinfunction "2_2") (pintype "passive"))
      (node (ref "U6") (pin "123") (pinfunction "PB8-BOOT0_123") (pintype "passive"))
    )
    (net (code "173") (name "/PB9") (class "Default")
      (node (ref "R127") (pin "1") (pinfunction "1_1") (pintype "passive"))
      (node (ref "U6") (pin "124") (pinfunction "PB9_124") (pintype "passive"))
    )
    (net (code "174") (name "/PB10") (class "Default")
      (node (ref "SB11") (pin "1") (pinfunction "1_1") (pintype "passive"))
      (node (ref "SB71") (pin "2") (pinfunction "2_2") (pintype "passive"))
      (node (ref "U6") (pin "62") (pinfunction "PB10_62") (pintype "passive"))
    )
    (net (code "175") (name "/PB11") (class "Default")
      (node (ref "SB10") (pin "1") (pinfunction "1_1") (pintype "passive"))
      (node (ref "SB67") (pin "2") (pinfunction "2_2") (pintype "passive"))
      (node (ref "SB8") (pin "1") (pinfunction "1_1") (pintype "passive"))
      (node (ref "U6") (pin "65") (pinfunction "PB11_65") (pintype "passive"))
    )
    (net (code "176") (name "/PB12") (class "Default")
      (node (ref "SB65") (pin "2") (pinfunction "2_2") (pintype "passive"))
      (node (ref "SB7") (pin "1") (pinfunction "1_1") (pintype "passive"))
      (node (ref "U6") (pin "66") (pinfunction "PB12_66") (pintype "passive"))
    )
    (net (code "177") (name "/PB13") (class "Default")
      (node (ref "SB5") (pin "1") (pinfunction "1_1") (pintype "passive"))
      (node (ref "SB63") (pin "2") (pinfunction "2_2") (pintype "passive"))
      (node (ref "U6") (pin "67") (pinfunction "PB13_67") (pintype "passive"))
    )
    (net (code "178") (name "/PB14") (class "Default")
      (node (ref "R35") (pin "1") (pinfunction "1_1") (pintype "passive"))
      (node (ref "U6") (pin "68") (pinfunction "PB14_68") (pintype "passive"))
    )
    (net (code "179") (name "/PB15") (class "Default")
      (node (ref "R36") (pin "1") (pinfunction "1_1") (pintype "passive"))
      (node (ref "U6") (pin "69") (pinfunction "PB15_69") (pintype "passive"))
    )
    (net (code "181") (name "/PC0") (class "Default")
      (node (ref "SB29") (pin "2") (pinfunction "2_2") (pintype "passive"))
      (node (ref "SB99") (pin "2") (pinfunction "2_2") (pintype "passive"))
      (node (ref "U6") (pin "22") (pinfunction "PC0_22") (pintype "passive"))
    )
    (net (code "182") (name "/PC1") (class "Default")
      (node (ref "R130") (pin "2") (pinfunction "2_2") (pintype "passive"))
      (node (ref "SB115") (pin "2") (pinfunction "2_2") (pintype "passive"))
      (node (ref "U6") (pin "23") (pinfunction "PC1_23") (pintype "passive"))
    )
    (net (code "183") (name "/PC2") (class "Default")
      (node (ref "R133") (pin "2") (pinfunction "2_2") (pintype "passive"))
      (node (ref "SB113") (pin "2") (pinfunction "2_2") (pintype "passive"))
      (node (ref "U6") (pin "24") (pinfunction "PC2_24") (pintype "passive"))
    )
    (net (code "184") (name "/PC3") (class "Default")
      (node (ref "R131") (pin "2") (pinfunction "2_2") (pintype "passive"))
      (node (ref "SB114") (pin "2") (pinfunction "2_2") (pintype "passive"))
      (node (ref "U6") (pin "25") (pinfunction "PC3_25") (pintype "passive"))
    )
    (net (code "185") (name "/PC4") (class "Default")
      (node (ref "R116") (pin "2") (pinfunction "2_2") (pintype "passive"))
      (node (ref "SB100") (pin "2") (pinfunction "2_2") (pintype "passive"))
      (node (ref "U6") (pin "37") (pinfunction "PC4_37") (pintype "passive"))
    )
    (net (code "186") (name "/PC5") (class "Default")
      (node (ref "SB20") (pin "2") (pinfunction "2_2") (pintype "passive"))
      (node (ref "U6") (pin "38") (pinfunction "PC5_38") (pintype "passive"))
    )
    (net (code "187") (name "/PC6") (class "Default")
      (node (ref "SB49") (pin "2") (pinfunction "2_2") (pintype "passive"))
      (node (ref "SB9") (pin "2") (pinfunction "2_2") (pintype "passive"))
      (node (ref "U6") (pin "80") (pinfunction "PC6_80") (pintype "passive"))
    )
    (net (code "188") (name "/PC7") (class "Default")
      (node (ref "SB50") (pin "2") (pinfunction "2_2") (pintype "passive"))
      (node (ref "SB6") (pin "2") (pinfunction "2_2") (pintype "passive"))
      (node (ref "U6") (pin "81") (pinfunction "PC7_81") (pintype "passive"))
    )
    (net (code "189") (name "/PC8") (class "Default")
      (node (ref "R26") (pin "2") (pinfunction "2_2") (pintype "passive"))
      (node (ref "SB51") (pin "2") (pinfunction "2_2") (pintype "passive"))
      (node (ref "U6") (pin "87") (pinfunction "PC8_87") (pintype "passive"))
    )
    (net (code "190") (name "/PC9") (class "Default")
      (node (ref "R49") (pin "2") (pinfunction "2_2") (pintype "passive"))
      (node (ref "U6") (pin "88") (pinfunction "PC9_88") (pintype "passive"))
    )
    (net (code "191") (name "/PC10") (class "Default")
      (node (ref "SB12") (pin "2") (pinfunction "2_2") (pintype "passive"))
      (node (ref "SB64") (pin "2") (pinfunction "2_2") (pintype "passive"))
      (node (ref "U6") (pin "100") (pinfunction "PC10_100") (pintype "passive"))
    )
    (net (code "192") (name "/PC11") (class "Default")
      (node (ref "SB13") (pin "2") (pinfunction "2_2") (pintype "passive"))
      (node (ref "SB68") (pin "2") (pinfunction "2_2") (pintype "passive"))
      (node (ref "U6") (pin "101") (pinfunction "PC11_101") (pintype "passive"))
    )
    (net (code "193") (name "/PC12") (class "Default")
      (node (ref "SB15") (pin "2") (pinfunction "2_2") (pintype "passive"))
      (node (ref "SB66") (pin "2") (pinfunction "2_2") (pintype "passive"))
      (node (ref "U6") (pin "102") (pinfunction "PC12_102") (pintype "passive"))
    )
    (net (code "194") (name "/PC13") (class "Default")
      (node (ref "R141") (pin "2") (pinfunction "2_2") (pintype "passive"))
      (node (ref "U6") (pin "7") (pinfunction "PC13_7") (pintype "passive"))
    )
    (net (code "195") (name "/PC14") (class "Default")
      (node (ref "U6") (pin "8") (pinfunction "PC14_-_OSC32_IN_8") (pintype "passive"))
    )
    (net (code "196") (name "/PC15") (class "Default")
      (node (ref "U6") (pin "9") (pinfunction "PC15_-_OSC32_OUT_9") (pintype "passive"))
    )
    (net (code "198") (name "/PD0") (class "Default")
      (node (ref "R83") (pin "1") (pinfunction "1_1") (pintype "passive"))
      (node (ref "U6") (pin "108") (pinfunction "PD0_108") (pintype "passive"))
    )
    (net (code "199") (name "/PD1") (class "Default")
      (node (ref "R85") (pin "1") (pinfunction "1_1") (pintype "passive"))
      (node (ref "U6") (pin "109") (pinfunction "PD1_109") (pintype "passive"))
    )
    (net (code "200") (name "/PD2") (class "Default")
      (node (ref "SB123") (pin "1") (pinfunction "1_1") (pintype "passive"))
      (node (ref "SB17") (pin "2") (pinfunction "2_2") (pintype "passive"))
      (node (ref "U6") (pin "112") (pinfunction "PD2_112") (pintype "passive"))
    )
    (net (code "201") (name "/PD3") (class "Default")
      (node (ref "R90") (pin "1") (pinfunction "1_1") (pintype "passive"))
      (node (ref "U6") (pin "113") (pinfunction "PD3_113") (pintype "passive"))
    )
    (net (code "202") (name "/PD4") (class "Default")
      (node (ref "R94") (pin "1") (pinfunction "1_1") (pintype "passive"))
      (node (ref "SB89") (pin "2") (pinfunction "2_2") (pintype "passive"))
      (node (ref "U6") (pin "114") (pinfunction "PD4_114") (pintype "passive"))
    )
    (net (code "203") (name "/PD5") (class "Default")
      (node (ref "R97") (pin "1") (pinfunction "1_1") (pintype "passive"))
      (node (ref "U6") (pin "115") (pinfunction "PD5_115") (pintype "passive"))
    )
    (net (code "204") (name "/PD6") (class "Default")
      (node (ref "R98") (pin "1") (pinfunction "1_1") (pintype "passive"))
      (node (ref "U6") (pin "116") (pinfunction "PD6_116") (pintype "passive"))
    )
    (net (code "205") (name "/PD7") (class "Default")
      (node (ref "R101") (pin "1") (pinfunction "1_1") (pintype "passive"))
      (node (ref "SB92") (pin "2") (pinfunction "2_2") (pintype "passive"))
      (node (ref "U6") (pin "117") (pinfunction "PD7_117") (pintype "passive"))
    )
    (net (code "206") (name "/PD8") (class "Default")
      (node (ref "R34") (pin "1") (pinfunction "1_1") (pintype "passive"))
      (node (ref "SB55") (pin "2") (pinfunction "2_2") (pintype "passive"))
      (node (ref "U6") (pin "70") (pinfunction "PD8_70") (pintype "passive"))
    )
    (net (code "207") (name "/PD9") (class "Default")
      (node (ref "R37") (pin "1") (pinfunction "1_1") (pintype "passive"))
      (node (ref "SB56") (pin "2") (pinfunction "2_2") (pintype "passive"))
      (node (ref "U6") (pin "71") (pinfunction "PD9_71") (pintype "passive"))
    )
    (net (code "208") (name "/PD10") (class "Default")
      (node (ref "R38") (pin "1") (pinfunction "1_1") (pintype "passive"))
      (node (ref "SB60") (pin "2") (pinfunction "2_2") (pintype "passive"))
      (node (ref "U6") (pin "72") (pinfunction "PD10_72") (pintype "passive"))
    )
    (net (code "209") (name "/PD11") (class "Default")
      (node (ref "R39") (pin "1") (pinfunction "1_1") (pintype "passive"))
      (node (ref "SB58") (pin "2") (pinfunction "2_2") (pintype "passive"))
      (node (ref "U6") (pin "73") (pinfunction "PD11_73") (pintype "passive"))
    )
    (net (code "210") (name "/PD12") (class "Default")
      (node (ref "R42") (pin "1") (pinfunction "1_1") (pintype "passive"))
      (node (ref "SB59") (pin "2") (pinfunction "2_2") (pintype "passive"))
      (node (ref "U6") (pin "74") (pinfunction "PD12_74") (pintype "passive"))
    )
    (net (code "211") (name "/PD13") (class "Default")
      (node (ref "R41") (pin "1") (pinfunction "1_1") (pintype "passive"))
      (node (ref "SB57") (pin "2") (pinfunction "2_2") (pintype "passive"))
      (node (ref "U6") (pin "75") (pinfunction "PD13_75") (pintype "passive"))
    )
    (net (code "212") (name "/PD14") (class "Default")
      (node (ref "R29") (pin "1") (pinfunction "1_1") (pintype "passive"))
      (node (ref "SB70") (pin "2") (pinfunction "2_2") (pintype "passive"))
      (node (ref "U6") (pin "76") (pinfunction "PD14_76") (pintype "passive"))
    )
    (net (code "213") (name "/PD15") (class "Default")
      (node (ref "R40") (pin "1") (pinfunction "1_1") (pintype "passive"))
      (node (ref "SB61") (pin "2") (pinfunction "2_2") (pintype "passive"))
      (node (ref "U6") (pin "77") (pinfunction "PD15_77") (pintype "passive"))
    )
    (net (code "215") (name "/PD_CC1") (class "Default")
      (node (ref "SB21") (pin "2") (pinfunction "2_2") (pintype "passive"))
    )
    (net (code "216") (name "/PD_CC2") (class "Default")
      (node (ref "SB96") (pin "2") (pinfunction "2_2") (pintype "passive"))
    )
    (net (code "217") (name "/PD_DBCC1") (class "Default")
      (node (ref "SB54") (pin "1") (pinfunction "1_1") (pintype "passive"))
    )
    (net (code "218") (name "/PD_DBCC2") (class "Default")
      (node (ref "SB53") (pin "1") (pinfunction "1_1") (pintype "passive"))
    )
    (net (code "219") (name "/PE0") (class "Default")
      (node (ref "R148") (pin "2") (pinfunction "2_2") (pintype "passive"))
      (node (ref "U6") (pin "125") (pinfunction "PE0_125") (pintype "passive"))
    )
    (net (code "220") (name "/PE1") (class "Default")
      (node (ref "R149") (pin "2") (pinfunction "2_2") (pintype "passive"))
      (node (ref "U6") (pin "126") (pinfunction "PE1_126") (pintype "passive"))
    )
    (net (code "221") (name "/PE2") (class "Default")
      (node (ref "R147") (pin "2") (pinfunction "2_2") (pintype "passive"))
      (node (ref "SB103") (pin "2") (pinfunction "2_2") (pintype "passive"))
      (node (ref "SB111") (pin "2") (pinfunction "2_2") (pintype "passive"))
      (node (ref "U6") (pin "1") (pinfunction "PE2_1") (pintype "passive"))
    )
    (net (code "222") (name "/PE3") (class "Default")
      (node (ref "R145") (pin "2") (pinfunction "2_2") (pintype "passive"))
      (node (ref "R146") (pin "2") (pinfunction "2_2") (pintype "passive"))
      (node (ref "SB110") (pin "2") (pinfunction "2_2") (pintype "passive"))
      (node (ref "SB118") (pin "2") (pinfunction "2_2") (pintype "passive"))
      (node (ref "U6") (pin "2") (pinfunction "PE3_2") (pintype "passive"))
    )
    (net (code "223") (name "/PE4") (class "Default")
      (node (ref "R143") (pin "2") (pinfunction "2_2") (pintype "passive"))
      (node (ref "R144") (pin "2") (pinfunction "2_2") (pintype "passive"))
      (node (ref "SB107") (pin "2") (pinfunction "2_2") (pintype "passive"))
      (node (ref "SB109") (pin "2") (pinfunction "2_2") (pintype "passive"))
      (node (ref "U6") (pin "3") (pinfunction "PE4_3") (pintype "passive"))
    )
    (net (code "224") (name "/PE5") (class "Default")
      (node (ref "SB28") (pin "2") (pinfunction "2_2") (pintype "passive"))
      (node (ref "SB97") (pin "2") (pinfunction "2_2") (pintype "passive"))
      (node (ref "U6") (pin "4") (pinfunction "PE5_4") (pintype "passive"))
    )
    (net (code "225") (name "/PE6") (class "Default")
      (node (ref "R142") (pin "2") (pinfunction "2_2") (pintype "passive"))
      (node (ref "U6") (pin "5") (pinfunction "PE6_5") (pintype "passive"))
    )
    (net (code "226") (name "/PE7") (class "Default")
      (node (ref "R84") (pin "2") (pinfunction "2_2") (pintype "passive"))
      (node (ref "SB83") (pin "2") (pinfunction "2_2") (pintype "passive"))
      (node (ref "U6") (pin "53") (pinfunction "PE7_53") (pintype "passive"))
    )
    (net (code "227") (name "/PE8") (class "Default")
      (node (ref "R82") (pin "2") (pinfunction "2_2") (pintype "passive"))
      (node (ref "SB79") (pin "2") (pinfunction "2_2") (pintype "passive"))
      (node (ref "U6") (pin "54") (pinfunction "PE8_54") (pintype "passive"))
    )
    (net (code "228") (name "/PE9") (class "Default")
      (node (ref "R79") (pin "2") (pinfunction "2_2") (pintype "passive"))
      (node (ref "SB78") (pin "2") (pinfunction "2_2") (pintype "passive"))
      (node (ref "U6") (pin "55") (pinfunction "PE9_55") (pintype "passive"))
    )
    (net (code "229") (name "/PE10") (class "Default")
      (node (ref "R75") (pin "2") (pinfunction "2_2") (pintype "passive"))
      (node (ref "SB77") (pin "2") (pinfunction "2_2") (pintype "passive"))
      (node (ref "U6") (pin "56") (pinfunction "PE10_56") (pintype "passive"))
    )
    (net (code "230") (name "/PE11") (class "Default")
      (node (ref "R71") (pin "2") (pinfunction "2_2") (pintype "passive"))
      (node (ref "SB76") (pin "2") (pinfunction "2_2") (pintype "passive"))
      (node (ref "U6") (pin "57") (pinfunction "PE11_57") (pintype "passive"))
    )
    (net (code "231") (name "/PE12") (class "Default")
      (node (ref "R69") (pin "2") (pinfunction "2_2") (pintype "passive"))
      (node (ref "SB74") (pin "2") (pinfunction "2_2") (pintype "passive"))
      (node (ref "U6") (pin "58") (pinfunction "PE12_58") (pintype "passive"))
    )
    (net (code "232") (name "/PE13") (class "Default")
      (node (ref "R63") (pin "2") (pinfunction "2_2") (pintype "passive"))
      (node (ref "SB73") (pin "2") (pinfunction "2_2") (pintype "passive"))
      (node (ref "U6") (pin "59") (pinfunction "PE13_59") (pintype "passive"))
    )
    (net (code "233") (name "/PE14") (class "Default")
      (node (ref "R62") (pin "2") (pinfunction "2_2") (pintype "passive"))
      (node (ref "SB72") (pin "2") (pinfunction "2_2") (pintype "passive"))
      (node (ref "U6") (pin "60") (pinfunction "PE14_60") (pintype "passive"))
    )
    (net (code "234") (name "/PE15") (class "Default")
      (node (ref "R60") (pin "2") (pinfunction "2_2") (pintype "passive"))
      (node (ref "SB69") (pin "2") (pinfunction "2_2") (pintype "passive"))
      (node (ref "U6") (pin "61") (pinfunction "PE15_61") (pintype "passive"))
    )
    (net (code "236") (name "/PF0") (class "Default")
      (node (ref "U6") (pin "19") (pinfunction "PF0_-_OSC_IN_19") (pintype "passive"))
    )
    (net (code "237") (name "/PF1") (class "Default")
      (node (ref "U6") (pin "20") (pinfunction "PF1_-_OSC_OUT_20") (pintype "passive"))
    )
    (net (code "238") (name "/PF2") (class "Default")
      (node (ref "R132") (pin "1") (pinfunction "1_1") (pintype "passive"))
      (node (ref "U6") (pin "26") (pinfunction "PF2_26") (pintype "passive"))
    )
    (net (code "239") (name "/PF3") (class "Default")
      (node (ref "R139") (pin "1") (pinfunction "1_1") (pintype "passive"))
      (node (ref "U6") (pin "10") (pinfunction "PF3_10") (pintype "passive"))
    )
    (net (code "240") (name "/PF4") (class "Default")
      (node (ref "R140") (pin "1") (pinfunction "1_1") (pintype "passive"))
      (node (ref "U6") (pin "11") (pinfunction "PF4_11") (pintype "passive"))
    )
    (net (code "241") (name "/PF5") (class "Default")
      (node (ref "R137") (pin "1") (pinfunction "1_1") (pintype "passive"))
      (node (ref "U6") (pin "14") (pinfunction "PF5_14") (pintype "passive"))
    )
    (net (code "242") (name "/PF6") (class "Default")
      (node (ref "R43") (pin "1") (pinfunction "1_1") (pintype "passive"))
      (node (ref "SB52") (pin "2") (pinfunction "2_2") (pintype "passive"))
      (node (ref "U6") (pin "97") (pinfunction "PF6_97") (pintype "passive"))
    )
    (net (code "243") (name "/PF7") (class "Default")
      (node (ref "R138") (pin "1") (pinfunction "1_1") (pintype "passive"))
      (node (ref "SB108") (pin "2") (pinfunction "2_2") (pintype "passive"))
      (node (ref "U6") (pin "15") (pinfunction "PF7_15") (pintype "passive"))
    )
    (net (code "244") (name "/PF8") (class "Default")
      (node (ref "R135") (pin "1") (pinfunction "1_1") (pintype "passive"))
      (node (ref "SB106") (pin "2") (pinfunction "2_2") (pintype "passive"))
      (node (ref "U6") (pin "16") (pinfunction "PF8_16") (pintype "passive"))
    )
    (net (code "245") (name "/PF9") (class "Default")
      (node (ref "R134") (pin "1") (pinfunction "1_1") (pintype "passive"))
      (node (ref "U6") (pin "17") (pinfunction "PF9_17") (pintype "passive"))
    )
    (net (code "246") (name "/PF10") (class "Default")
      (node (ref "R136") (pin "1") (pinfunction "1_1") (pintype "passive"))
      (node (ref "SB112") (pin "2") (pinfunction "2_2") (pintype "passive"))
      (node (ref "U6") (pin "18") (pinfunction "PF10_18") (pintype "passive"))
    )
    (net (code "247") (name "/PF11") (class "Default")
      (node (ref "R96") (pin "1") (pinfunction "1_1") (pintype "passive"))
      (node (ref "U6") (pin "48") (pinfunction "PF11_48") (pintype "passive"))
    )
    (net (code "248") (name "/PF12") (class "Default")
      (node (ref "R93") (pin "1") (pinfunction "1_1") (pintype "passive"))
      (node (ref "U6") (pin "49") (pinfunction "PF12_49") (pintype "passive"))
    )
    (net (code "249") (name "/PF13") (class "Default")
      (node (ref "R89") (pin "1") (pinfunction "1_1") (pintype "passive"))
      (node (ref "U6") (pin "50") (pinfunction "PF13_50") (pintype "passive"))
    )
    (net (code "250") (name "/PF14") (class "Default")
      (node (ref "R88") (pin "1") (pinfunction "1_1") (pintype "passive"))
      (node (ref "U6") (pin "51") (pinfunction "PF14_51") (pintype "passive"))
    )
    (net (code "251") (name "/PF15") (class "Default")
      (node (ref "R87") (pin "1") (pinfunction "1_1") (pintype "passive"))
      (node (ref "U6") (pin "52") (pinfunction "PF15_52") (pintype "passive"))
    )
    (net (code "253") (name "/PG0") (class "Default")
      (node (ref "R48") (pin "1") (pinfunction "1_1") (pintype "passive"))
      (node (ref "U6") (pin "82") (pinfunction "PG0_82") (pintype "passive"))
    )
    (net (code "254") (name "/PG1") (class "Default")
      (node (ref "R28") (pin "1") (pinfunction "1_1") (pintype "passive"))
      (node (ref "U6") (pin "83") (pinfunction "PG1_83") (pintype "passive"))
    )
    (net (code "255") (name "/PG2") (class "Default")
      (node (ref "R50") (pin "1") (pinfunction "1_1") (pintype "passive"))
      (node (ref "U6") (pin "84") (pinfunction "PG2_84") (pintype "passive"))
    )
    (net (code "256") (name "/PG3") (class "Default")
      (node (ref "R27") (pin "1") (pinfunction "1_1") (pintype "passive"))
      (node (ref "U6") (pin "85") (pinfunction "PG3_85") (pintype "passive"))
    )
    (net (code "257") (name "/PG4") (class "Default")
      (node (ref "R53") (pin "1") (pinfunction "1_1") (pintype "passive"))
      (node (ref "U6") (pin "86") (pinfunction "PG4_86") (pintype "passive"))
    )
    (net (code "258") (name "/PG5") (class "Default")
      (node (ref "R68") (pin "1") (pinfunction "1_1") (pintype "passive"))
      (node (ref "U6") (pin "103") (pinfunction "PG5_103") (pintype "passive"))
    )
    (net (code "259") (name "/PG6") (class "Default")
      (node (ref "R70") (pin "1") (pinfunction "1_1") (pintype "passive"))
      (node (ref "U6") (pin "104") (pinfunction "PG6_104") (pintype "passive"))
    )
    (net (code "260") (name "/PG7") (class "Default")
      (node (ref "R74") (pin "1") (pinfunction "1_1") (pintype "passive"))
      (node (ref "U6") (pin "105") (pinfunction "PG7_105") (pintype "passive"))
    )
    (net (code "261") (name "/PG8") (class "Default")
      (node (ref "R78") (pin "1") (pinfunction "1_1") (pintype "passive"))
      (node (ref "U6") (pin "106") (pinfunction "PG8_106") (pintype "passive"))
    )
    (net (code "262") (name "/PG9") (class "Default")
      (node (ref "R81") (pin "1") (pinfunction "1_1") (pintype "passive"))
      (node (ref "U6") (pin "107") (pinfunction "PG9_107") (pintype "passive"))
    )
    (net (code "264") (name "/QSPI_BK1_IO0") (class "Default")
      (node (ref "R102") (pin "2") (pinfunction "2_2") (pintype "passive"))
    )
    (net (code "265") (name "/QSPI_BK1_IO1") (class "Default")
      (node (ref "R108") (pin "2") (pinfunction "2_2") (pintype "passive"))
    )
    (net (code "266") (name "/QSPI_BK1_IO2") (class "Default")
      (node (ref "R118") (pin "1") (pinfunction "1_1") (pintype "passive"))
    )
    (net (code "267") (name "/QSPI_BK1_IO3") (class "Default")
      (node (ref "R121") (pin "1") (pinfunction "1_1") (pintype "passive"))
    )
    (net (code "268") (name "/QSPI_BK1_NCS") (class "Default")
      (node (ref "R150") (pin "1") (pinfunction "1_1") (pintype "passive"))
    )
    (net (code "269") (name "/QSPI_BK2_IO0") (class "Default")
      (node (ref "R130") (pin "1") (pinfunction "1_1") (pintype "passive"))
    )
    (net (code "270") (name "/QSPI_BK2_IO1") (class "Default")
      (node (ref "R133") (pin "1") (pinfunction "1_1") (pintype "passive"))
    )
    (net (code "271") (name "/QSPI_BK2_IO2") (class "Default")
      (node (ref "R131") (pin "1") (pinfunction "1_1") (pintype "passive"))
    )
    (net (code "272") (name "/QSPI_BK2_IO3") (class "Default")
      (node (ref "R116") (pin "1") (pinfunction "1_1") (pintype "passive"))
    )
    (net (code "273") (name "/QSPI_BK2_NCS") (class "Default")
      (node (ref "R90") (pin "2") (pinfunction "2_2") (pintype "passive"))
    )
    (net (code "274") (name "/QSPI_CLK") (class "Default")
      (node (ref "R129") (pin "1") (pinfunction "1_1") (pintype "passive"))
    )
    (net (code "275") (name "/RS485_DIR") (class "Default")
      (node (ref "SB123") (pin "2") (pinfunction "2_2") (pintype "passive"))
    )
    (net (code "276") (name "/SAI_FS_A") (class "Default")
      (node (ref "SB107") (pin "1") (pinfunction "1_1") (pintype "passive"))
    )
    (net (code "277") (name "/SAI_MCLK_A") (class "Default")
      (node (ref "SB111") (pin "1") (pinfunction "1_1") (pintype "passive"))
    )
    (net (code "278") (name "/SAI_SCK_A") (class "Default")
      (node (ref "R30") (pin "1") (pinfunction "1_1") (pintype "passive"))
    )
    (net (code "279") (name "/SAI_SD_A") (class "Default")
      (node (ref "R98") (pin "2") (pinfunction "2_2") (pintype "passive"))
    )
    (net (code "280") (name "/SAI_SD_B") (class "Default")
      (node (ref "SB110") (pin "1") (pinfunction "1_1") (pintype "passive"))
    )
    (net (code "281") (name "/SOURCE_EN") (class "Default")
      (node (ref "SB13") (pin "1") (pinfunction "1_1") (pintype "passive"))
    )
    (net (code "282") (name "/SPI2_MISO") (class "Default")
      (node (ref "R35") (pin "2") (pinfunction "2_2") (pintype "passive"))
    )
    (net (code "283") (name "/SPI2_MOSI") (class "Default")
      (node (ref "R36") (pin "2") (pinfunction "2_2") (pintype "passive"))
    )
    (net (code "284") (name "/SPI2_SCK") (class "Default")
      (node (ref "R134") (pin "2") (pinfunction "2_2") (pintype "passive"))
    )
    (net (code "285") (name "/SmartCard_CLK") (class "Default")
      (node (ref "SB15") (pin "1") (pinfunction "1_1") (pintype "passive"))
    )
    (net (code "286") (name "/SmartCard_IO") (class "Default")
      (node (ref "SB12") (pin "1") (pinfunction "1_1") (pintype "passive"))
    )
    (net (code "287") (name "/TAMPER_KEY") (class "Default")
      (node (ref "R141") (pin "1") (pinfunction "1_1") (pintype "passive"))
    )
    (net (code "288") (name "/TRACECLK") (class "Default")
      (node (ref "R147") (pin "1") (pinfunction "1_1") (pintype "passive"))
    )
    (net (code "289") (name "/TRACED0") (class "Default")
      (node (ref "R145") (pin "1") (pinfunction "1_1") (pintype "passive"))
    )
    (net (code "290") (name "/TRACED1") (class "Default")
      (node (ref "R144") (pin "1") (pinfunction "1_1") (pintype "passive"))
    )
    (net (code "291") (name "/TRACED2") (class "Default")
      (node (ref "SB28") (pin "1") (pinfunction "1_1") (pintype "passive"))
    )
    (net (code "292") (name "/TRACED3") (class "Default")
      (node (ref "R142") (pin "1") (pinfunction "1_1") (pintype "passive"))
    )
    (net (code "293") (name "/USART1_RX") (class "Default")
      (node (ref "SB3") (pin "1") (pinfunction "1_1") (pintype "passive"))
    )
    (net (code "294") (name "/USART1_TX") (class "Default")
      (node (ref "SB4") (pin "1") (pinfunction "1_1") (pintype "passive"))
    )
    (net (code "295") (name "/USB_DM") (class "Default")
      (node (ref "R46") (pin "1") (pinfunction "1_1") (pintype "passive"))
    )
    (net (code "296") (name "/USB_DP") (class "Default")
      (node (ref "R45") (pin "1") (pinfunction "1_1") (pintype "passive"))
    )
    (net (code "297") (name "/VSENSE") (class "Default")
      (node (ref "SB29") (pin "1") (pinfunction "1_1") (pintype "passive"))
    )
    (net (code "298") (name "/uSD_CS") (class "Default")
      (node (ref "R135") (pin "2") (pinfunction "2_2") (pintype "passive"))
    )
    (net (code "310") (name "VDD") (class "Default")
      (node (ref "R73") (pin "2") (pinfunction "2_2") (pintype "passive"))
      (node (ref "R80") (pin "2") (pinfunction "2_2") (pintype "passive"))
    )
  )
)
